# Venato_Schematic_v1.net
KiCad netlist of a schematic drawn in Altium Designer
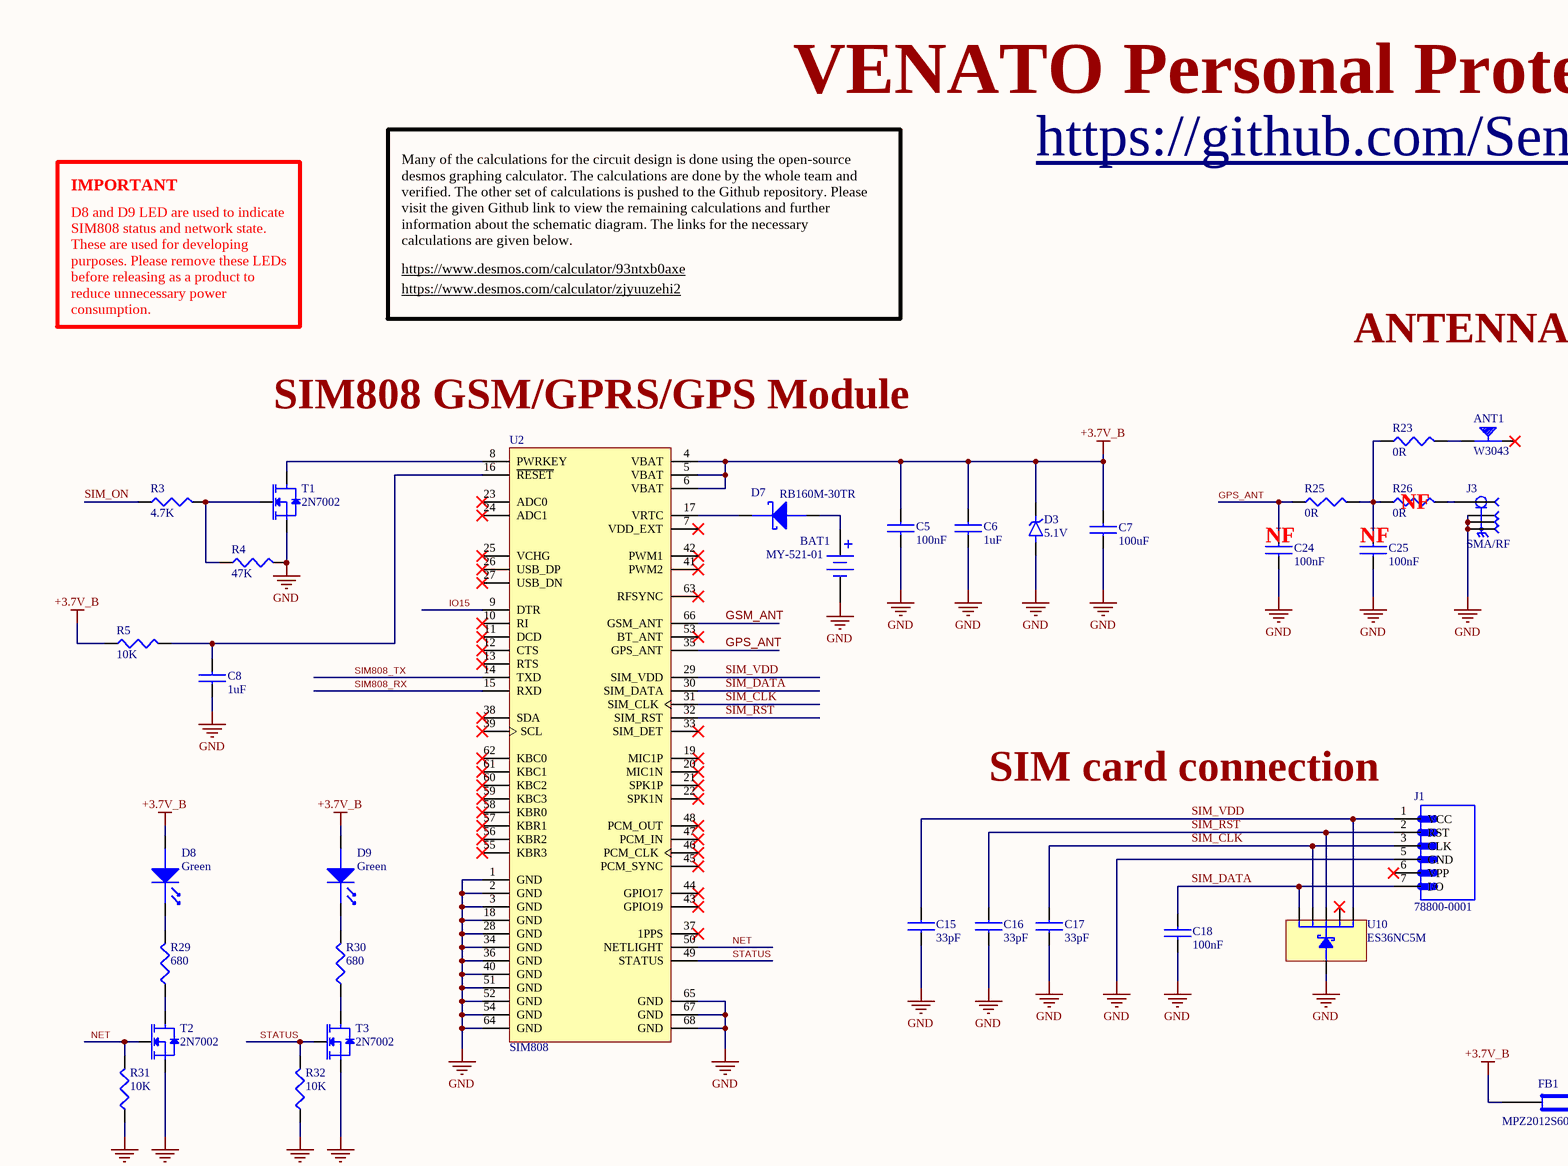
[diagram p0: Venato_Schematic_v1.SchDoc, top left]
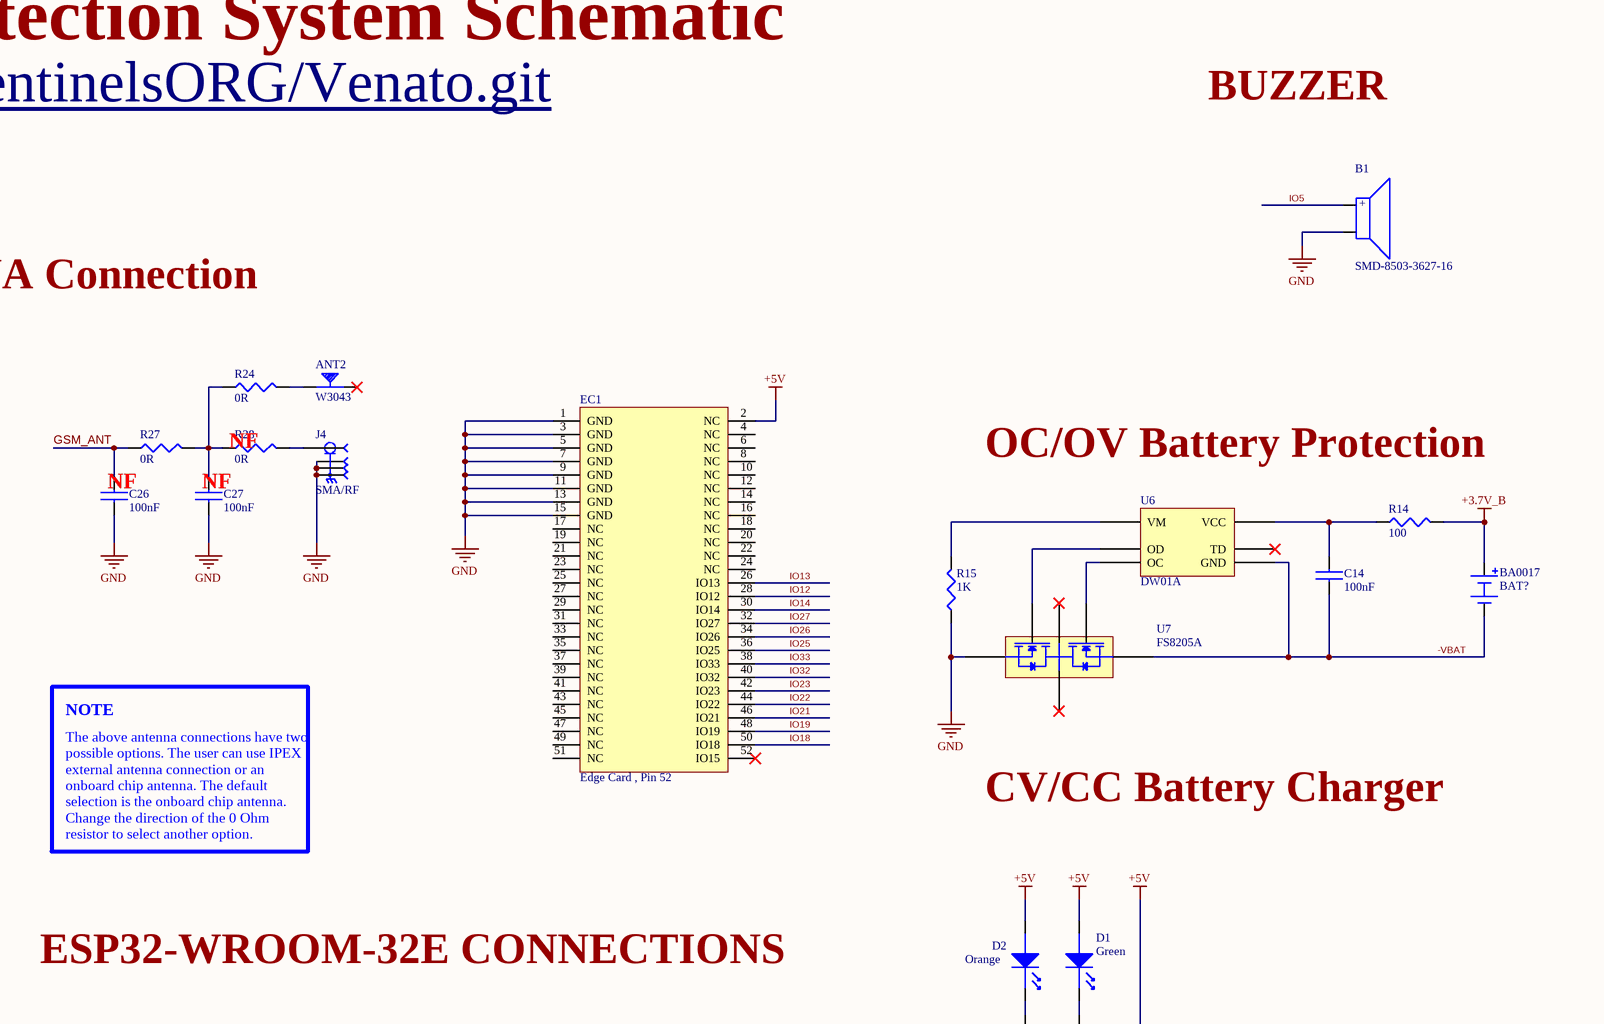
[diagram p1: Venato_Schematic_v1.SchDoc, top right]
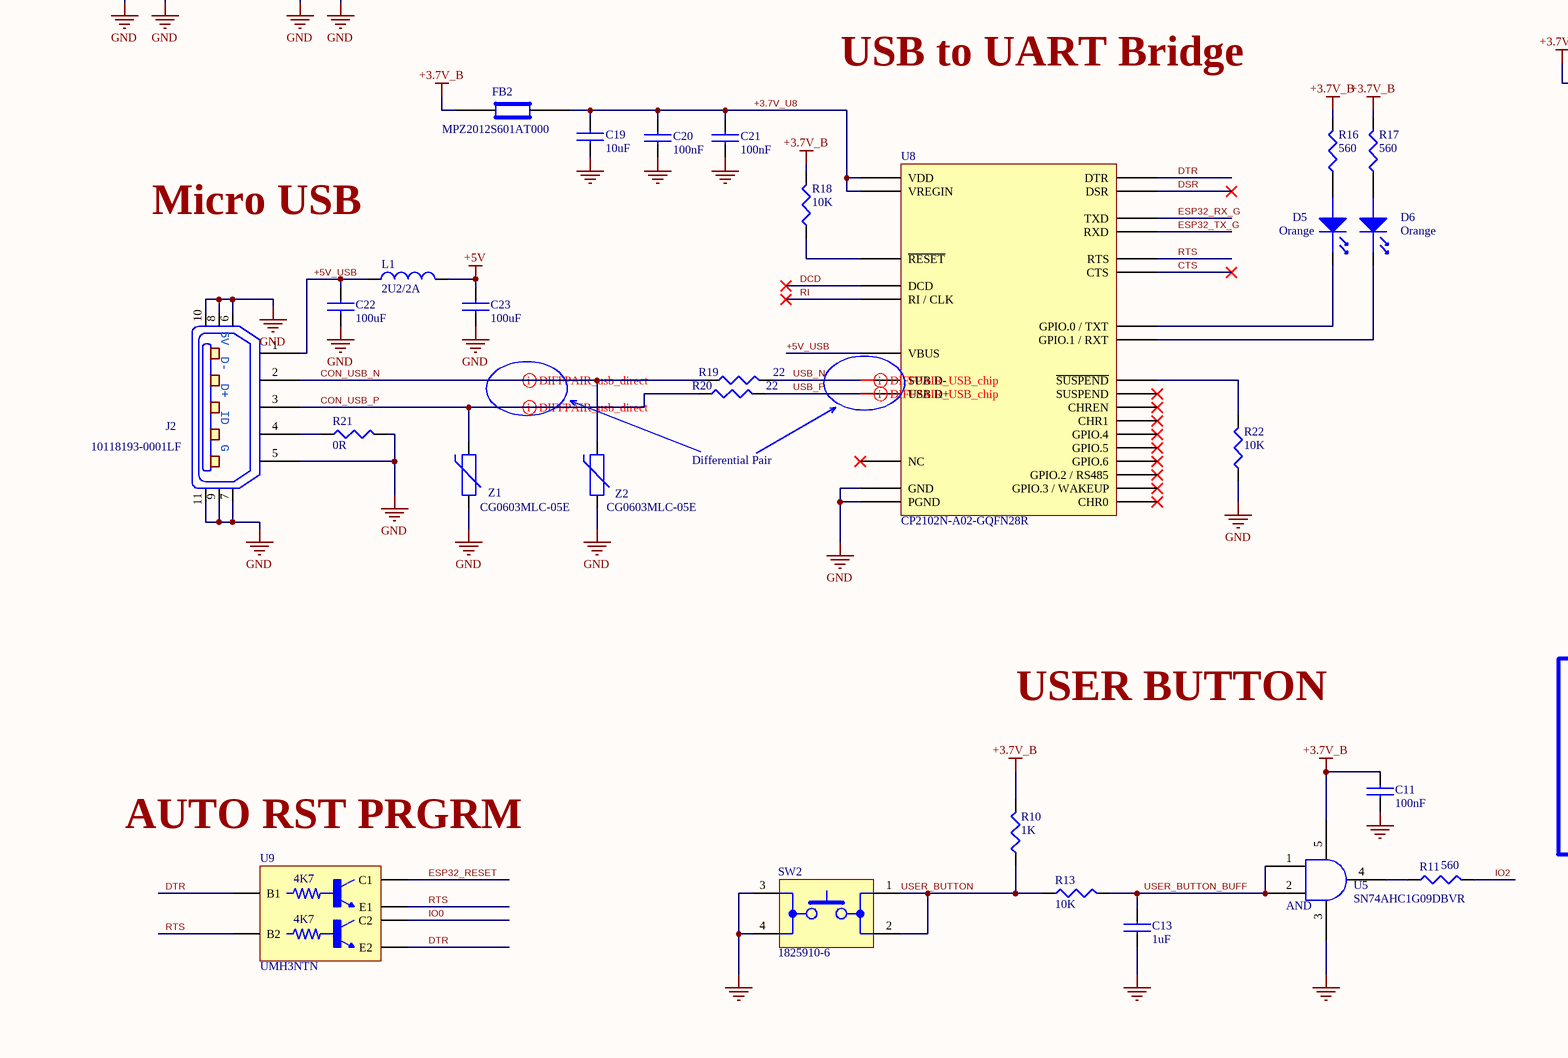
[diagram p2: Venato_Schematic_v1.SchDoc, bottom left]
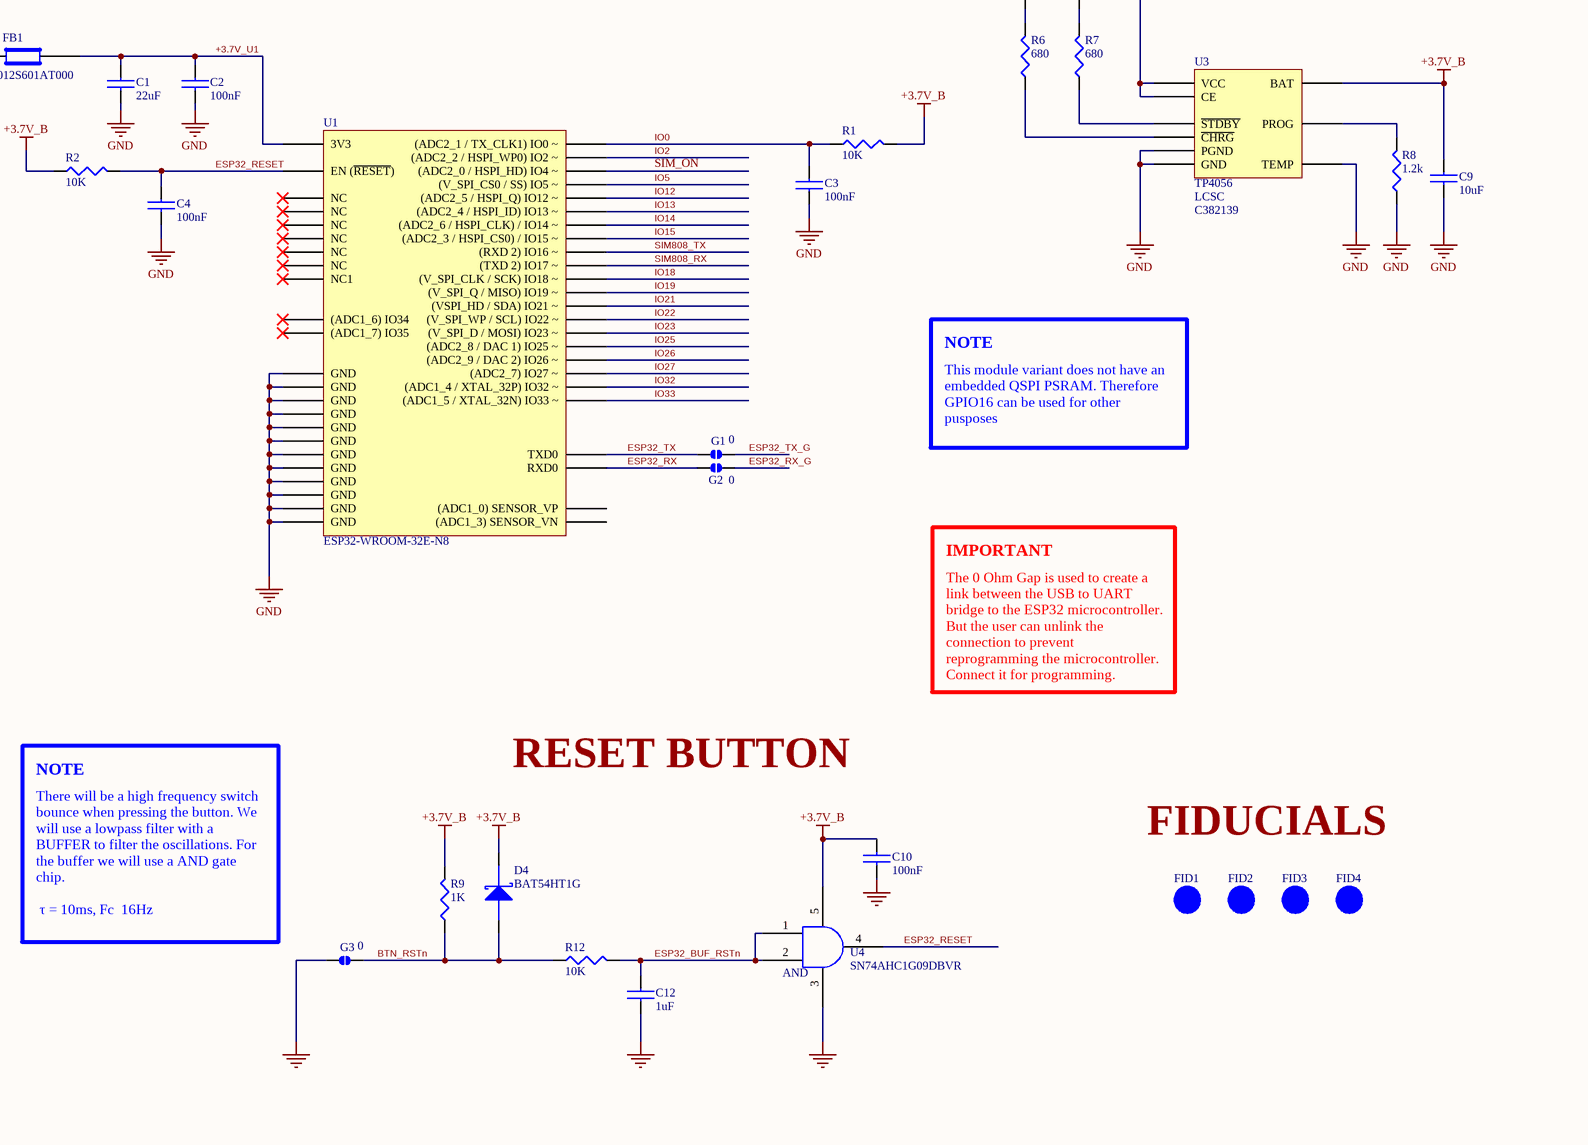
[diagram p3: Venato_Schematic_v1.SchDoc, bottom right]

(export (version "E")
  (design (tool "Eeschema 10.0.6"))
  (components
    (comp (ref "ANT1")
      (value "W3043")
      (footprint "W3010")
      (description "Antenna Ceramic Monopole 4dB Gain 2483.5MHz SMD")
      (fields (field (name "MANUFACTURER") "Pulse"))
      (libsource (lib "schmaticSMDv1") (part "W3043"))
    )
    (comp (ref "ANT2")
      (value "W3043")
      (footprint "W3010")
      (description "Antenna Ceramic Monopole 4dB Gain 2483.5MHz SMD")
      (fields (field (name "MANUFACTURER") "Pulse"))
      (libsource (lib "schmaticSMDv1") (part "W3043"))
    )
    (comp (ref "B1")
      (value "SMD-8503-3627-16")
      (footprint "SMD-8503-3627-16O")
      (description "SMD Buzzers ROHS")
      (fields (field (name "MANUFACTURER") "S&S"))
      (libsource (lib "schmaticSMDv1") (part "SMD-8503-3627-16"))
    )
    (comp (ref "BA0017")
      (value "BAT?")
      (footprint "Battery")
      (libsource (lib "schmaticSMDv1") (part "BA0017"))
    )
    (comp (ref "BAT1")
      (value "MY-521-01")
      (footprint "My-521-01")
      (description "Battery button SR521 SMD Battery Connectors ROHS")
      (fields (field (name "MANUFACTURER") "MYoung"))
      (libsource (lib "schmaticSMDv1") (part "MY-521-01"))
    )
    (comp (ref "C1")
      (value "22uF")
      (footprint "C0805")
      (description "CAP CER 22UF 25V X5R 0805")
      (fields
        (field (name "MANUFACTURER") "Samsung")
        (field (name "MANUFACTURER PART NUMBER") "CL21A226MAQNNNE")
      )
      (libsource (lib "schmaticSMDv1") (part "CL21A226MAQNNNE"))
    )
    (comp (ref "C2")
      (value "100nF")
      (footprint "C0805")
      (description "Cap Ceramic 0.1uF 50V X7R 10% Pad SMD 0805 125°C Automotive T/R")
      (fields
        (field (name "MANUFACTURER") "TDK")
        (field (name "MANUFACTURER PART NUMBER") "CGA4J2X7R1H104K125AM")
      )
      (libsource (lib "schmaticSMDv1") (part "CGA4J2X7R1H104K125AM"))
    )
    (comp (ref "C3")
      (value "100nF")
      (footprint "C0805")
      (description "Cap Ceramic 0.1uF 50V X7R 10% Pad SMD 0805 125°C Automotive T/R")
      (fields
        (field (name "MANUFACTURER") "TDK")
        (field (name "MANUFACTURER PART NUMBER") "CGA4J2X7R1H104K125AM")
      )
      (libsource (lib "schmaticSMDv1") (part "CGA4J2X7R1H104K125AM"))
    )
    (comp (ref "C4")
      (value "100nF")
      (footprint "C0805")
      (description "Cap Ceramic 0.1uF 50V X7R 10% Pad SMD 0805 125°C Automotive T/R")
      (fields
        (field (name "MANUFACTURER") "TDK")
        (field (name "MANUFACTURER PART NUMBER") "CGA4J2X7R1H104K125AM")
      )
      (libsource (lib "schmaticSMDv1") (part "CGA4J2X7R1H104K125AM"))
    )
    (comp (ref "C5")
      (value "100nF")
      (footprint "C0805")
      (description "Cap Ceramic 0.1uF 50V X7R 10% Pad SMD 0805 125°C Automotive T/R")
      (fields
        (field (name "MANUFACTURER") "TDK")
        (field (name "MANUFACTURER PART NUMBER") "CGA4J2X7R1H104K125AM")
      )
      (libsource (lib "schmaticSMDv1") (part "CGA4J2X7R1H104K125AM"))
    )
    (comp (ref "C6")
      (value "1uF")
      (footprint "C0805")
      (description "0805 1 uF 50 V ±10% Tolerance X7R Multilayer Ceramic Chip Capacitor")
      (fields
        (field (name "MANUFACTURER") "Murata")
        (field (name "MANUFACTURER PART NUMBER") "GRM21BR71H105KA12L")
      )
      (libsource (lib "schmaticSMDv1") (part "GRM21BR71H105KA12L"))
    )
    (comp (ref "C7")
      (value "100uF")
      (footprint "C0805")
      (description "0805 100 uF 6.3 V ±20% Tolerance X5R Multilayer Ceramic Chip Capacitor")
      (fields
        (field (name "MANUFACTURER") "Murata")
        (field (name "MANUFACTURER PART NUMBER") "GRM21BR60J107ME15L")
      )
      (libsource (lib "schmaticSMDv1") (part "GRM21BR60J107ME15L"))
    )
    (comp (ref "C8")
      (value "1uF")
      (footprint "C0805")
      (fields
        (field (name "MANUFACTURER") "TDK")
        (field (name "MANUFACTURER PART NUMBER") "C2012X5R1E105K125AA")
        (field (name "TOLERANCE") "10%")
      )
      (libsource (lib "schmaticSMDv1") (part "C2012X5R1E105K125AA"))
    )
    (comp (ref "C9")
      (value "10uF")
      (footprint "C0805")
      (description "Cap Ceramic 10uF 10V X7S 20% Pad SMD 0805 125°C Low ESR Automotive T/R")
      (fields
        (field (name "MANUFACTURER") "TDK")
        (field (name "MANUFACTURER PART NUMBER") "CGA4J3X7S1A106M125AB")
      )
      (libsource (lib "schmaticSMDv1") (part "CGA4J3X7S1A106M125AB"))
    )
    (comp (ref "C10")
      (value "100nF")
      (footprint "C0805")
      (description "Cap Ceramic 0.1uF 50V X7R 10% Pad SMD 0805 125°C Automotive T/R")
      (fields
        (field (name "MANUFACTURER") "TDK")
        (field (name "MANUFACTURER PART NUMBER") "CGA4J2X7R1H104K125AM")
      )
      (libsource (lib "atmega_shlib") (part "CGA4J2X7R1H104K125AM"))
    )
    (comp (ref "C11")
      (value "100nF")
      (footprint "C0805")
      (description "Cap Ceramic 0.1uF 50V X7R 10% Pad SMD 0805 125°C Automotive T/R")
      (fields
        (field (name "MANUFACTURER") "TDK")
        (field (name "MANUFACTURER PART NUMBER") "CGA4J2X7R1H104K125AM")
      )
      (libsource (lib "atmega_shlib") (part "CGA4J2X7R1H104K125AM"))
    )
    (comp (ref "C12")
      (value "1uF")
      (footprint "C0805")
      (fields
        (field (name "MANUFACTURER") "TDK")
        (field (name "MANUFACTURER PART NUMBER") "C2012X5R1E105K125AA")
        (field (name "TOLERANCE") "10%")
      )
      (libsource (lib "schmaticSMDv1") (part "C2012X5R1E105K125AA"))
    )
    (comp (ref "C13")
      (value "1uF")
      (footprint "C0805")
      (fields
        (field (name "MANUFACTURER") "TDK")
        (field (name "MANUFACTURER PART NUMBER") "C2012X5R1E105K125AA")
        (field (name "TOLERANCE") "10%")
      )
      (libsource (lib "schmaticSMDv1") (part "C2012X5R1E105K125AA"))
    )
    (comp (ref "C14")
      (value "100nF")
      (footprint "C0805")
      (description "Cap Ceramic 0.1uF 50V X7R 10% Pad SMD 0805 125°C Automotive T/R")
      (fields
        (field (name "MANUFACTURER") "TDK")
        (field (name "MANUFACTURER PART NUMBER") "CGA4J2X7R1H104K125AM")
      )
      (libsource (lib "schmaticSMDv1") (part "CGA4J2X7R1H104K125AM"))
    )
    (comp (ref "C15")
      (value "33pF")
      (footprint "C0805")
      (description "Cap Ceramic 33pF 50V C0G 5% SMD 0805 125C T/R")
      (fields
        (field (name "MANUFACTURER") "Yageo")
        (field (name "MANUFACTURER PART NUMBER") "CC0805JRNPO9BN330")
      )
      (libsource (lib "schmaticSMDv1") (part "CC0805JRNPO9BN330"))
    )
    (comp (ref "C16")
      (value "33pF")
      (footprint "C0805")
      (description "Cap Ceramic 33pF 50V C0G 5% SMD 0805 125C T/R")
      (fields
        (field (name "MANUFACTURER") "Yageo")
        (field (name "MANUFACTURER PART NUMBER") "CC0805JRNPO9BN330")
      )
      (libsource (lib "schmaticSMDv1") (part "CC0805JRNPO9BN330"))
    )
    (comp (ref "C17")
      (value "33pF")
      (footprint "C0805")
      (description "Cap Ceramic 33pF 50V C0G 5% SMD 0805 125C T/R")
      (fields
        (field (name "MANUFACTURER") "Yageo")
        (field (name "MANUFACTURER PART NUMBER") "CC0805JRNPO9BN330")
      )
      (libsource (lib "schmaticSMDv1") (part "CC0805JRNPO9BN330"))
    )
    (comp (ref "C18")
      (value "100nF")
      (footprint "C0805")
      (description "Cap Ceramic 0.1uF 50V X7R 10% Pad SMD 0805 125°C Automotive T/R")
      (fields
        (field (name "MANUFACTURER") "TDK")
        (field (name "MANUFACTURER PART NUMBER") "CGA4J2X7R1H104K125AM")
      )
      (libsource (lib "schmaticSMDv1") (part "CGA4J2X7R1H104K125AM"))
    )
    (comp (ref "C19")
      (value "10uF")
      (footprint "C0805")
      (description "Cap Ceramic 10uF 10V X7S 20% Pad SMD 0805 125°C Low ESR Automotive T/R")
      (fields
        (field (name "MANUFACTURER") "TDK")
        (field (name "MANUFACTURER PART NUMBER") "CGA4J3X7S1A106M125AB")
      )
      (libsource (lib "atmega_shlib") (part "CGA4J3X7S1A106M125AB"))
    )
    (comp (ref "C20")
      (value "100nF")
      (footprint "C0805")
      (description "Cap Ceramic 0.1uF 50V X7R 10% Pad SMD 0805 125°C Automotive T/R")
      (fields
        (field (name "MANUFACTURER") "TDK")
        (field (name "MANUFACTURER PART NUMBER") "CGA4J2X7R1H104K125AM")
      )
      (libsource (lib "atmega_shlib") (part "CGA4J2X7R1H104K125AM"))
    )
    (comp (ref "C21")
      (value "100nF")
      (footprint "C0805")
      (description "Cap Ceramic 0.1uF 50V X7R 10% Pad SMD 0805 125°C Automotive T/R")
      (fields
        (field (name "MANUFACTURER") "TDK")
        (field (name "MANUFACTURER PART NUMBER") "CGA4J2X7R1H104K125AM")
      )
      (libsource (lib "atmega_shlib") (part "CGA4J2X7R1H104K125AM"))
    )
    (comp (ref "C22")
      (value "100uF")
      (footprint "C0805")
      (description "0805 100 uF 6.3 V ±20% Tolerance X5R Multilayer Ceramic Chip Capacitor")
      (fields
        (field (name "MANUFACTURER") "Murata")
        (field (name "MANUFACTURER PART NUMBER") "GRM21BR60J107ME15L")
      )
      (libsource (lib "schmaticSMDv1") (part "GRM21BR60J107ME15L"))
    )
    (comp (ref "C23")
      (value "100uF")
      (footprint "C0805")
      (description "0805 100 uF 6.3 V ±20% Tolerance X5R Multilayer Ceramic Chip Capacitor")
      (fields
        (field (name "MANUFACTURER") "Murata")
        (field (name "MANUFACTURER PART NUMBER") "GRM21BR60J107ME15L")
      )
      (libsource (lib "schmaticSMDv1") (part "GRM21BR60J107ME15L"))
    )
    (comp (ref "C24")
      (value "100nF")
      (footprint "C0805")
      (description "Cap Ceramic 0.1uF 50V X7R 10% Pad SMD 0805 125°C Automotive T/R")
      (fields
        (field (name "MANUFACTURER") "TDK")
        (field (name "MANUFACTURER PART NUMBER") "CGA4J2X7R1H104K125AM")
      )
      (libsource (lib "schmaticSMDv1") (part "CGA4J2X7R1H104K125AM"))
    )
    (comp (ref "C25")
      (value "100nF")
      (footprint "C0805")
      (description "Cap Ceramic 0.1uF 50V X7R 10% Pad SMD 0805 125°C Automotive T/R")
      (fields
        (field (name "MANUFACTURER") "TDK")
        (field (name "MANUFACTURER PART NUMBER") "CGA4J2X7R1H104K125AM")
      )
      (libsource (lib "schmaticSMDv1") (part "CGA4J2X7R1H104K125AM"))
    )
    (comp (ref "C26")
      (value "100nF")
      (footprint "C0805")
      (description "Cap Ceramic 0.1uF 50V X7R 10% Pad SMD 0805 125°C Automotive T/R")
      (fields
        (field (name "MANUFACTURER") "TDK")
        (field (name "MANUFACTURER PART NUMBER") "CGA4J2X7R1H104K125AM")
      )
      (libsource (lib "schmaticSMDv1") (part "CGA4J2X7R1H104K125AM"))
    )
    (comp (ref "C27")
      (value "100nF")
      (footprint "C0805")
      (description "Cap Ceramic 0.1uF 50V X7R 10% Pad SMD 0805 125°C Automotive T/R")
      (fields
        (field (name "MANUFACTURER") "TDK")
        (field (name "MANUFACTURER PART NUMBER") "CGA4J2X7R1H104K125AM")
      )
      (libsource (lib "schmaticSMDv1") (part "CGA4J2X7R1H104K125AM"))
    )
    (comp (ref "D1")
      (value "Green")
      (footprint "LED0603")
      (description "LED Single Chip Green 570nm 20mA 2-Pin 0603 T/R")
      (fields
        (field (name "MANUFACTURER") "Osram Opto")
        (field (name "MANUFACTURER PART NUMBER") "LGL29K-G2J1-24-Z")
      )
      (libsource (lib "schmaticSMDv1") (part "LGL29K-G2J1-24-Z"))
    )
    (comp (ref "D2")
      (value "Orange")
      (footprint "LED0603")
      (description "Smartled Orange Lc")
      (fields
        (field (name "MANUFACTURER") "Osram Opto")
        (field (name "MANUFACTURER PART NUMBER") "LOL29K-H2K1-24-Z")
      )
      (libsource (lib "schmaticSMDv1") (part "LOL29K-H2K1-24-Z"))
    )
    (comp (ref "D3")
      (value "5.1V")
      (footprint "SOD323")
      (description "Zener Single Diode, 5.1 V, 200 Mw, Sod-323, 6 %, 2, 150 C Rohs Compliant: Yes")
      (fields
        (field (name "MANUFACTURER") "Multicomp")
        (field (name "MANUFACTURER PART NUMBER") "BZT52C5V1S")
      )
      (libsource (lib "schmaticSMDv1") (part "BZT52C5V1S"))
    )
    (comp (ref "D4")
      (value "BAT54HT1G")
      (footprint "SOD323")
      (description "Small Signal Schottky Diode, Single, 30 V, 200 Ma, 800 Mv, 600 Ma, 150 C")
      (fields (field (name "MANUFACTURER") "ON Semiconductor / Fairchild"))
      (libsource (lib "atmega_shlib") (part "BAT54HT1G"))
    )
    (comp (ref "D5")
      (value "Orange")
      (footprint "LED0603")
      (description "Smartled Orange Lc")
      (fields
        (field (name "MANUFACTURER") "Osram Opto")
        (field (name "MANUFACTURER PART NUMBER") "LOL29K-H2K1-24-Z")
      )
      (libsource (lib "atmega_shlib") (part "LOL29K-H2K1-24-Z"))
    )
    (comp (ref "D6")
      (value "Orange")
      (footprint "LED0603")
      (description "Smartled Orange Lc")
      (fields
        (field (name "MANUFACTURER") "Osram Opto")
        (field (name "MANUFACTURER PART NUMBER") "LOL29K-H2K1-24-Z")
      )
      (libsource (lib "atmega_shlib") (part "LOL29K-H2K1-24-Z"))
    )
    (comp (ref "D7")
      (value "RB160M-30TR")
      (footprint "SOD123")
      (description "DIODE SCHOTTKY 30V 1A PMDU")
      (fields (field (name "MANUFACTURER") "Rohm"))
      (libsource (lib "schmaticSMDv1") (part "RB160M-30TR"))
    )
    (comp (ref "D8")
      (value "Green")
      (footprint "LED0603")
      (description "LED Single Chip Green 570nm 20mA 2-Pin 0603 T/R")
      (fields
        (field (name "MANUFACTURER") "Osram Opto")
        (field (name "MANUFACTURER PART NUMBER") "LGL29K-G2J1-24-Z")
      )
      (libsource (lib "schmaticSMDv1") (part "LGL29K-G2J1-24-Z"))
    )
    (comp (ref "D9")
      (value "Green")
      (footprint "LED0603")
      (description "LED Single Chip Green 570nm 20mA 2-Pin 0603 T/R")
      (fields
        (field (name "MANUFACTURER") "Osram Opto")
        (field (name "MANUFACTURER PART NUMBER") "LGL29K-G2J1-24-Z")
      )
      (libsource (lib "schmaticSMDv1") (part "LGL29K-G2J1-24-Z"))
    )
    (comp (ref "EC1")
      (value "Edge Card , Pin 52")
      (footprint "Edge Connector")
      (libsource (lib "schmaticSMDv1") (part "EdgeCard"))
    )
    (comp (ref "FB1")
      (value "MPZ2012S601AT000")
      (footprint "C0805")
      (description "Ferrite Beads Multi-Layer Power 600Ohm 25% 100MHz 2A 100mOhm DCR 0805 T/R")
      (fields (field (name "MANUFACTURER") "TDK"))
      (libsource (lib "schmaticSMDv1") (part "MPZ2012S601AT000"))
    )
    (comp (ref "FB2")
      (value "MPZ2012S601AT000")
      (footprint "C0805")
      (description "Ferrite Beads Multi-Layer Power 600Ohm 25% 100MHz 2A 100mOhm DCR 0805 T/R")
      (fields (field (name "MANUFACTURER") "TDK"))
      (libsource (lib "atmega_shlib") (part "MPZ2012S601AT000"))
    )
    (comp (ref "FID1")
      (value "FID_1MM")
      (footprint "FID_x_420")
      (description "Fisushal 1MM")
      (libsource (lib "atmega_shlib") (part "FID_1MM"))
    )
    (comp (ref "FID2")
      (value "FID_1MM")
      (footprint "FID_x_420")
      (description "Fisushal 1MM")
      (libsource (lib "atmega_shlib") (part "FID_1MM"))
    )
    (comp (ref "FID3")
      (value "FID_1MM")
      (footprint "FID_x_420")
      (description "Fisushal 1MM")
      (libsource (lib "atmega_shlib") (part "FID_1MM"))
    )
    (comp (ref "FID4")
      (value "FID_1MM")
      (footprint "FID_x_420")
      (description "Fisushal 1MM")
      (libsource (lib "atmega_shlib") (part "FID_1MM"))
    )
    (comp (ref "G1")
      (value "0")
      (footprint "R0805_no_3d")
      (description "This is a gap that diconects line. you can connect it using soldier")
      (libsource (lib "schmaticSMDv1") (part "0Ohm gap"))
    )
    (comp (ref "G2")
      (value "0")
      (footprint "R0805_no_3d")
      (description "This is a gap that diconects line. you can connect it using soldier")
      (libsource (lib "schmaticSMDv1") (part "0Ohm gap"))
    )
    (comp (ref "G3")
      (value "0")
      (footprint "R0805_no_3d")
      (description "This is a gap that diconects line. you can connect it using soldier")
      (libsource (lib "schmaticSMDv1") (part "0Ohm gap"))
    )
    (comp (ref "J1")
      (value "78800-0001")
      (footprint "SIM")
      (description "Vertical Surface Mount Memory & SIM Card Connector; with SMT Termination")
      (fields (field (name "MANUFACTURER") "Molex"))
      (libsource (lib "schmaticSMDv1") (part "78800-0001"))
    )
    (comp (ref "J2")
      (value "10118193-0001LF")
      (footprint "10118193-0001LF")
      (description "FCI Right Angle Surface Mount Mount Female USB Connector; 100 V ac; 1.8A")
      (fields (field (name "MANUFACTURER") "Amphenol ICC / FCI"))
      (libsource (lib "atmega_shlib") (part "10118193-0001LF"))
    )
    (comp (ref "J3")
      (value "SMA/RF")
      (footprint "IPEX_20579-001E")
      (description "SMD RF Connectors / Coaxial Connectors ROHS")
      (libsource (lib "schmaticSMDv1") (part "Ipex"))
    )
    (comp (ref "J4")
      (value "SMA/RF")
      (footprint "IPEX_20579-001E")
      (description "SMD RF Connectors / Coaxial Connectors ROHS")
      (libsource (lib "schmaticSMDv1") (part "Ipex"))
    )
    (comp (ref "L1")
      (value "2U2/2A")
      (footprint "CL_inductor")
      (description "Inductor RF Chip Wirewound 2.2uH 20% 100KHz 1.13A 0.104Ohm DCR 1210 T/R")
      (fields
        (field (name "MANUFACTURER") "KEMET")
        (field (name "MANUFACTURER PART NUMBER") "L1210R2R2MDWIT")
      )
      (libsource (lib "atmega_shlib") (part "L1210R2R2MDWIT"))
    )
    (comp (ref "R1")
      (value "10K")
      (footprint "R0805")
      (description "Res SMD 0805 10K 1% 0.125W T.C.100PPM")
      (fields
        (field (name "MANUFACTURER") "Yageo")
        (field (name "MANUFACTURER PART NUMBER") "RC0805FR-0710KL")
      )
      (libsource (lib "schmaticSMDv1") (part "RC0805FR-0710KL"))
    )
    (comp (ref "R2")
      (value "10K")
      (footprint "R0805")
      (description "Res SMD 0805 10K 1% 0.125W T.C.100PPM")
      (fields
        (field (name "MANUFACTURER") "Yageo")
        (field (name "MANUFACTURER PART NUMBER") "RC0805FR-0710KL")
      )
      (libsource (lib "schmaticSMDv1") (part "RC0805FR-0710KL"))
    )
    (comp (ref "R3")
      (value "4.7K")
      (footprint "R0805")
      (description "Res Thick Film 0805 4.7K Ohm 5% 0.125W(1/8W) ±100ppm/C Pad SMD T/R")
      (fields
        (field (name "MANUFACTURER") "Yageo")
        (field (name "MANUFACTURER PART NUMBER") "RC0805JR-074K7L")
      )
      (libsource (lib "schmaticSMDv1") (part "RC0805JR-074K7L"))
    )
    (comp (ref "R4")
      (value "47K")
      (footprint "R0805")
      (description "Res Thick Film 0805 47K Ohm 5% 1/8W Ý100ppm/ÝC SMD Paper T/R")
      (fields
        (field (name "MANUFACTURER") "Yageo")
        (field (name "MANUFACTURER PART NUMBER") "RC0805JR-0747KL")
      )
      (libsource (lib "schmaticSMDv1") (part "RC0805JR-0747KL"))
    )
    (comp (ref "R5")
      (value "10K")
      (footprint "R0805")
      (description "Res SMD 0805 10K 1% 0.125W T.C.100PPM")
      (fields
        (field (name "MANUFACTURER") "Yageo")
        (field (name "MANUFACTURER PART NUMBER") "RC0805FR-0710KL")
      )
      (libsource (lib "schmaticSMDv1") (part "RC0805FR-0710KL"))
    )
    (comp (ref "R6")
      (value "680")
      (footprint "R0805")
      (description "Res Thick Film 0805 680 Ohm 5% 0.125W(1/8W) ±200ppm/C Pad SMD Automotive T/R")
      (fields
        (field (name "MANUFACTURER") "Stackpole Electronics")
        (field (name "MANUFACTURER PART NUMBER") "RMCF0805JT680R")
      )
      (libsource (lib "schmaticSMDv1") (part "RMCF0805JT680R"))
    )
    (comp (ref "R7")
      (value "680")
      (footprint "R0805")
      (description "Res Thick Film 0805 680 Ohm 5% 0.125W(1/8W) ±200ppm/C Pad SMD Automotive T/R")
      (fields
        (field (name "MANUFACTURER") "Stackpole Electronics")
        (field (name "MANUFACTURER PART NUMBER") "RMCF0805JT680R")
      )
      (libsource (lib "schmaticSMDv1") (part "RMCF0805JT680R"))
    )
    (comp (ref "R8")
      (value "1.2k")
      (footprint "R0805")
      (description "Res Thick Film 0805 1.2K Ohm 1% 0.125W(1/8W) ±100ppm/C Pad SMD T/R")
      (fields
        (field (name "MANUFACTURER") "Yageo")
        (field (name "MANUFACTURER PART NUMBER") "RC0805FR-071K2L")
      )
      (libsource (lib "schmaticSMDv1") (part "RC0805FR-071K2L"))
    )
    (comp (ref "R9")
      (value "1K")
      (footprint "R0805")
      (description "Res Thick Film 0805 1KOhm 1% 0.125W(1/8W) 100ppm/C Epoxy Pad SMD T/R")
      (fields
        (field (name "MANUFACTURER") "Yageo")
        (field (name "MANUFACTURER PART NUMBER") "RC0805FR-071KL")
      )
      (libsource (lib "schmaticSMDv1") (part "RC0805FR-071KL"))
    )
    (comp (ref "R10")
      (value "1K")
      (footprint "R0805")
      (description "Res Thick Film 0805 1KOhm 1% 0.125W(1/8W) 100ppm/C Epoxy Pad SMD T/R")
      (fields
        (field (name "MANUFACTURER") "Yageo")
        (field (name "MANUFACTURER PART NUMBER") "RC0805FR-071KL")
      )
      (libsource (lib "schmaticSMDv1") (part "RC0805FR-071KL"))
    )
    (comp (ref "R11")
      (value "560")
      (footprint "R0805")
      (description "Res General Purpose Thick Film 0805 560 Ohm 1% 1/8W ±100ppm/°C Molded Paper T/R")
      (fields
        (field (name "MANUFACTURER") "Yageo")
        (field (name "MANUFACTURER PART NUMBER") "RC0805FR-07560RL")
      )
      (libsource (lib "atmega_shlib") (part "RC0805FR-07560RL"))
    )
    (comp (ref "R12")
      (value "10K")
      (footprint "R0805")
      (description "Res SMD 0805 10K 1% 0.125W T.C.100PPM")
      (fields
        (field (name "MANUFACTURER") "Yageo")
        (field (name "MANUFACTURER PART NUMBER") "RC0805FR-0710KL")
      )
      (libsource (lib "schmaticSMDv1") (part "RC0805FR-0710KL"))
    )
    (comp (ref "R13")
      (value "10K")
      (footprint "R0805")
      (description "Res SMD 0805 10K 1% 0.125W T.C.100PPM")
      (fields
        (field (name "MANUFACTURER") "Yageo")
        (field (name "MANUFACTURER PART NUMBER") "RC0805FR-0710KL")
      )
      (libsource (lib "schmaticSMDv1") (part "RC0805FR-0710KL"))
    )
    (comp (ref "R14")
      (value "100")
      (footprint "R0805")
      (description "Res Thick Film 0805 100 Ohm 1% 1/8W ±100ppm/°C Molded SMD Paper T/R")
      (fields
        (field (name "MANUFACTURER") "Yageo")
        (field (name "MANUFACTURER PART NUMBER") "RC0805FR-07100RL")
      )
      (libsource (lib "schmaticSMDv1") (part "RC0805FR-07100RL"))
    )
    (comp (ref "R15")
      (value "1K")
      (footprint "R0805")
      (description "Res Thick Film 0805 1KOhm 1% 0.125W(1/8W) 100ppm/C Epoxy Pad SMD T/R")
      (fields
        (field (name "MANUFACTURER") "Yageo")
        (field (name "MANUFACTURER PART NUMBER") "RC0805FR-071KL")
      )
      (libsource (lib "schmaticSMDv1") (part "RC0805FR-071KL"))
    )
    (comp (ref "R16")
      (value "560")
      (footprint "R0805")
      (description "Res General Purpose Thick Film 0805 560 Ohm 1% 1/8W ±100ppm/°C Molded Paper T/R")
      (fields
        (field (name "MANUFACTURER") "Yageo")
        (field (name "MANUFACTURER PART NUMBER") "RC0805FR-07560RL")
      )
      (libsource (lib "atmega_shlib") (part "RC0805FR-07560RL"))
    )
    (comp (ref "R17")
      (value "560")
      (footprint "R0805")
      (description "Res General Purpose Thick Film 0805 560 Ohm 1% 1/8W ±100ppm/°C Molded Paper T/R")
      (fields
        (field (name "MANUFACTURER") "Yageo")
        (field (name "MANUFACTURER PART NUMBER") "RC0805FR-07560RL")
      )
      (libsource (lib "atmega_shlib") (part "RC0805FR-07560RL"))
    )
    (comp (ref "R18")
      (value "10K")
      (footprint "R0805")
      (description "Res SMD 0805 10K 1% 0.125W T.C.100PPM")
      (fields
        (field (name "MANUFACTURER") "Yageo")
        (field (name "MANUFACTURER PART NUMBER") "RC0805FR-0710KL")
      )
      (libsource (lib "atmega_shlib") (part "RC0805FR-0710KL"))
    )
    (comp (ref "R19")
      (value "22")
      (footprint "R0805")
      (description "Res SMD 0805 22R 1% 0.125W T.C.100PPM")
      (fields
        (field (name "MANUFACTURER") "Yageo")
        (field (name "MANUFACTURER PART NUMBER") "RC0805FR-0722RL")
      )
      (libsource (lib "atmega_shlib") (part "RC0805FR-0722RL"))
    )
    (comp (ref "R20")
      (value "22")
      (footprint "R0805")
      (description "Res SMD 0805 22R 1% 0.125W T.C.100PPM")
      (fields
        (field (name "MANUFACTURER") "Yageo")
        (field (name "MANUFACTURER PART NUMBER") "RC0805FR-0722RL")
      )
      (libsource (lib "atmega_shlib") (part "RC0805FR-0722RL"))
    )
    (comp (ref "R21")
      (value "0R")
      (footprint "R0805")
      (description "RC Series 0805 0.125 W 0 Ohm Jumper Surface Mount Thick Film Chip Resistor")
      (fields
        (field (name "MANUFACTURER") "Yageo")
        (field (name "MANUFACTURER PART NUMBER") "RC0805JR-070RL")
      )
      (libsource (lib "atmega_shlib") (part "RC0805JR-070RL"))
    )
    (comp (ref "R22")
      (value "10K")
      (footprint "R0805")
      (description "Res SMD 0805 10K 1% 0.125W T.C.100PPM")
      (fields
        (field (name "MANUFACTURER") "Yageo")
        (field (name "MANUFACTURER PART NUMBER") "RC0805FR-0710KL")
      )
      (libsource (lib "atmega_shlib") (part "RC0805FR-0710KL"))
    )
    (comp (ref "R23")
      (value "0R")
      (footprint "R0805")
      (description "RC Series 0805 0.125 W 0 Ohm Jumper Surface Mount Thick Film Chip Resistor")
      (fields
        (field (name "MANUFACTURER") "Yageo")
        (field (name "MANUFACTURER PART NUMBER") "RC0805JR-070RL")
      )
      (libsource (lib "schmaticSMDv1") (part "RC0805JR-070RL"))
    )
    (comp (ref "R24")
      (value "0R")
      (footprint "R0805")
      (description "RC Series 0805 0.125 W 0 Ohm Jumper Surface Mount Thick Film Chip Resistor")
      (fields
        (field (name "MANUFACTURER") "Yageo")
        (field (name "MANUFACTURER PART NUMBER") "RC0805JR-070RL")
      )
      (libsource (lib "schmaticSMDv1") (part "RC0805JR-070RL"))
    )
    (comp (ref "R25")
      (value "0R")
      (footprint "R0805")
      (description "RC Series 0805 0.125 W 0 Ohm Jumper Surface Mount Thick Film Chip Resistor")
      (fields
        (field (name "MANUFACTURER") "Yageo")
        (field (name "MANUFACTURER PART NUMBER") "RC0805JR-070RL")
      )
      (libsource (lib "schmaticSMDv1") (part "RC0805JR-070RL"))
    )
    (comp (ref "R26")
      (value "0R")
      (footprint "R0805")
      (description "RC Series 0805 0.125 W 0 Ohm Jumper Surface Mount Thick Film Chip Resistor")
      (fields
        (field (name "MANUFACTURER") "Yageo")
        (field (name "MANUFACTURER PART NUMBER") "RC0805JR-070RL")
      )
      (libsource (lib "schmaticSMDv1") (part "RC0805JR-070RL"))
    )
    (comp (ref "R27")
      (value "0R")
      (footprint "R0805")
      (description "RC Series 0805 0.125 W 0 Ohm Jumper Surface Mount Thick Film Chip Resistor")
      (fields
        (field (name "MANUFACTURER") "Yageo")
        (field (name "MANUFACTURER PART NUMBER") "RC0805JR-070RL")
      )
      (libsource (lib "schmaticSMDv1") (part "RC0805JR-070RL"))
    )
    (comp (ref "R28")
      (value "0R")
      (footprint "R0805")
      (description "RC Series 0805 0.125 W 0 Ohm Jumper Surface Mount Thick Film Chip Resistor")
      (fields
        (field (name "MANUFACTURER") "Yageo")
        (field (name "MANUFACTURER PART NUMBER") "RC0805JR-070RL")
      )
      (libsource (lib "schmaticSMDv1") (part "RC0805JR-070RL"))
    )
    (comp (ref "R29")
      (value "680")
      (footprint "R0805")
      (description "Res Thick Film 0805 680 Ohm 5% 0.125W(1/8W) ±200ppm/C Pad SMD Automotive T/R")
      (fields
        (field (name "MANUFACTURER") "Stackpole Electronics")
        (field (name "MANUFACTURER PART NUMBER") "RMCF0805JT680R")
      )
      (libsource (lib "schmaticSMDv1") (part "RMCF0805JT680R"))
    )
    (comp (ref "R30")
      (value "680")
      (footprint "R0805")
      (description "Res Thick Film 0805 680 Ohm 5% 0.125W(1/8W) ±200ppm/C Pad SMD Automotive T/R")
      (fields
        (field (name "MANUFACTURER") "Stackpole Electronics")
        (field (name "MANUFACTURER PART NUMBER") "RMCF0805JT680R")
      )
      (libsource (lib "schmaticSMDv1") (part "RMCF0805JT680R"))
    )
    (comp (ref "R31")
      (value "10K")
      (footprint "R0805")
      (description "Res SMD 0805 10K 1% 0.125W T.C.100PPM")
      (fields
        (field (name "MANUFACTURER") "Yageo")
        (field (name "MANUFACTURER PART NUMBER") "RC0805FR-0710KL")
      )
      (libsource (lib "schmaticSMDv1") (part "RC0805FR-0710KL"))
    )
    (comp (ref "R32")
      (value "10K")
      (footprint "R0805")
      (description "Res SMD 0805 10K 1% 0.125W T.C.100PPM")
      (fields
        (field (name "MANUFACTURER") "Yageo")
        (field (name "MANUFACTURER PART NUMBER") "RC0805FR-0710KL")
      )
      (libsource (lib "schmaticSMDv1") (part "RC0805FR-0710KL"))
    )
    (comp (ref "SW2")
      (value "1825910-6")
      (footprint "DIP41825910-6")
      (description "Switch Tactile OFF (ON) SPST Round Button PC Pins 0.05A 24VDC 1.57N Thru-Hole Loose")
      (fields (field (name "MANUFACTURER") "TE Connectivity Alcoswitch"))
      (libsource (lib "atmega_shlib") (part "1825910-6"))
    )
    (comp (ref "T1")
      (value "2N7002")
      (footprint "TRANS_MMBT2907A")
      (description "Transistor Mosfet N-ch 60V 0.3A 3-PIN SOT-23 T/r")
      (libsource (lib "schmaticSMDv1") (part "2N7002"))
    )
    (comp (ref "T2")
      (value "2N7002")
      (footprint "TRANS_MMBT2907A")
      (description "Transistor Mosfet N-ch 60V 0.3A 3-PIN SOT-23 T/r")
      (libsource (lib "schmaticSMDv1") (part "2N7002"))
    )
    (comp (ref "T3")
      (value "2N7002")
      (footprint "TRANS_MMBT2907A")
      (description "Transistor Mosfet N-ch 60V 0.3A 3-PIN SOT-23 T/r")
      (libsource (lib "schmaticSMDv1") (part "2N7002"))
    )
    (comp (ref "U1")
      (value "ESP32-WROOM-32E-N8")
      (footprint "XCVR_ESP32-WROOM-32E_(16MB)")
      (fields (field (name "MANUFACTURER") "Espressif Systems"))
      (libsource (lib "schmaticSMDv1") (part "ESP32-WROOM-32E-N8"))
    )
    (comp (ref "U2")
      (value "SIM808")
      (footprint "XCVR_SIM808")
      (description "GSM/GPRS + GPS + Bluetooth Module SIM808 S2-1060C-Z1F05 SIMCOM; 850/900/1800/1900MHz")
      (libsource (lib "schmaticSMDv1") (part "SIM808"))
    )
    (comp (ref "U3")
      (value "TP4056")
      (footprint "SOP_8")
      (description "Res Thick Film 0805 1.2K Ohm 1% 0.125W(1/8W) ±100ppm/C Pad SMD T/R")
      (fields
        (field (name "MANUFACTURER") "TPOWER")
        (field (name "SUPPLIER 1") "LCSC")
        (field (name "SUPPLIER PART NUMBER 1") "C382139")
        (field (name "TOLERANCE") "1%")
      )
      (libsource (lib "schmaticSMDv1") (part "TP4056"))
    )
    (comp (ref "U4")
      (value "SN74AHC1G09DBVR")
      (footprint "DBV_SOT_5")
      (description "Single 2-input, 2-V to 5.5-V AND gate with open-drain outputs 5-SOT-23 -55 to 125")
      (fields (field (name "MANUFACTURER") "Texas Instruments"))
      (libsource (lib "atmega_shlib") (part "SN74AHC1G09DBVR"))
    )
    (comp (ref "U5")
      (value "SN74AHC1G09DBVR")
      (footprint "DBV_SOT_5")
      (description "Single 2-input, 2-V to 5.5-V AND gate with open-drain outputs 5-SOT-23 -55 to 125")
      (fields (field (name "MANUFACTURER") "Texas Instruments"))
      (libsource (lib "atmega_shlib") (part "SN74AHC1G09DBVR"))
    )
    (comp (ref "U6")
      (value "DW01A")
      (footprint "SOT23-6")
      (description "SOT-23-6L Battery Management ICs ROHS")
      (fields (field (name "MANUFACTURER") "TF"))
      (libsource (lib "schmaticSMDv1") (part "DW01A"))
    )
    (comp (ref "U7")
      (value "FS8205A")
      (footprint "SOT23-6")
      (fields (field (name "MANUFACTURER") "Tech Public"))
      (libsource (lib "schmaticSMDv1") (part "FS8205A"))
    )
    (comp (ref "U8")
      (value "CP2102N-A02-GQFN28R")
      (footprint "WFQFN-28")
      (description "Full Speed USB to UART Bridge USB 2.0 3.3V T/R Automotive 28-Pin QFN EP")
      (fields (field (name "MANUFACTURER") "Silicon Labs"))
      (libsource (lib "schmaticSMDv1") (part "CP2102N-A02-GQFN28R"))
    )
    (comp (ref "U9")
      (value "UMH3NTN")
      (footprint "SOT-363")
      (description "TRANS 2NPN PREBIAS 0.15W UMT6")
      (fields (field (name "MANUFACTURER") "Rohm"))
      (libsource (lib "schmaticSMDv1") (part "UMH3NTN"))
    )
    (comp (ref "U10")
      (value "ES36NC5M")
      (footprint "SOT-363")
      (description "SOT-363 ESD Protection Devices ROHS")
      (fields (field (name "MANUFACTURER") "JESTEK"))
      (libsource (lib "schmaticSMDv1") (part "ES36NC5M"))
    )
    (comp (ref "Z1")
      (value "CG0603MLC-05E")
      (footprint "R0603")
      (description "ESD Suppressor Multilayer Varistor 5V Automotive 2-Pin Case 0603(1608Metric) T/R")
      (fields (field (name "MANUFACTURER") "Bourns") (field (name "VOLTAGE") "5V"))
      (libsource (lib "atmega_shlib") (part "CG0603MLC-05E"))
    )
    (comp (ref "Z2")
      (value "CG0603MLC-05E")
      (footprint "R0603")
      (description "ESD Suppressor Multilayer Varistor 5V Automotive 2-Pin Case 0603(1608Metric) T/R")
      (fields (field (name "MANUFACTURER") "Bourns") (field (name "VOLTAGE") "5V"))
      (libsource (lib "atmega_shlib") (part "CG0603MLC-05E"))
    )
  )
  (nets
    (net (code "1") (name "+3.7V_B") (class "Default")
      (node (ref "BA0017") (pin "1") (pinfunction "1_1") (pintype "passive"))
      (node (ref "C10") (pin "2") (pinfunction "2_2") (pintype "passive"))
      (node (ref "C11") (pin "2") (pinfunction "2_2") (pintype "passive"))
      (node (ref "C5") (pin "2") (pinfunction "2_2") (pintype "passive"))
      (node (ref "C6") (pin "2") (pinfunction "2_2") (pintype "passive"))
      (node (ref "C7") (pin "2") (pinfunction "2_2") (pintype "passive"))
      (node (ref "C9") (pin "2") (pinfunction "2_2") (pintype "passive"))
      (node (ref "D3") (pin "1") (pinfunction "1_1") (pintype "passive"))
      (node (ref "D4") (pin "1") (pinfunction "Ca_1") (pintype "passive"))
      (node (ref "D8") (pin "2") (pinfunction "An_2") (pintype "passive"))
      (node (ref "D9") (pin "2") (pinfunction "An_2") (pintype "passive"))
      (node (ref "FB1") (pin "1") (pinfunction "1_1") (pintype "passive"))
      (node (ref "FB2") (pin "1") (pinfunction "1_1") (pintype "passive"))
      (node (ref "R1") (pin "1") (pinfunction "1_1") (pintype "passive"))
      (node (ref "R10") (pin "2") (pinfunction "2_2") (pintype "passive"))
      (node (ref "R14") (pin "2") (pinfunction "2_2") (pintype "passive"))
      (node (ref "R16") (pin "2") (pinfunction "2_2") (pintype "passive"))
      (node (ref "R17") (pin "2") (pinfunction "2_2") (pintype "passive"))
      (node (ref "R18") (pin "2") (pinfunction "2_2") (pintype "passive"))
      (node (ref "R2") (pin "1") (pinfunction "1_1") (pintype "passive"))
      (node (ref "R5") (pin "1") (pinfunction "1_1") (pintype "passive"))
      (node (ref "R9") (pin "2") (pinfunction "2_2") (pintype "passive"))
      (node (ref "U2") (pin "4") (pinfunction "VBAT_4") (pintype "passive"))
      (node (ref "U2") (pin "5") (pinfunction "VBAT_5") (pintype "passive"))
      (node (ref "U2") (pin "6") (pinfunction "VBAT_6") (pintype "passive"))
      (node (ref "U3") (pin "5") (pinfunction "BAT_5") (pintype "passive"))
      (node (ref "U4") (pin "5") (pinfunction "5_5") (pintype "passive"))
      (node (ref "U5") (pin "5") (pinfunction "5_5") (pintype "passive"))
    )
    (net (code "2") (name "+5V") (class "Default")
      (node (ref "C23") (pin "2") (pinfunction "2_2") (pintype "passive"))
      (node (ref "D1") (pin "2") (pinfunction "An_2") (pintype "passive"))
      (node (ref "D2") (pin "2") (pinfunction "An_2") (pintype "passive"))
      (node (ref "EC1") (pin "2") (pinfunction "NC_2") (pintype "passive"))
      (node (ref "L1") (pin "2") (pinfunction "2_2") (pintype "passive"))
      (node (ref "U3") (pin "4") (pinfunction "VCC_4") (pintype "passive"))
      (node (ref "U3") (pin "8") (pinfunction "CE_8") (pintype "passive"))
    )
    (net (code "3") (name "/+3.7V_U1") (class "Default")
      (node (ref "C1") (pin "2") (pinfunction "2_2") (pintype "passive"))
      (node (ref "C2") (pin "2") (pinfunction "2_2") (pintype "passive"))
      (node (ref "FB1") (pin "2") (pinfunction "2_2") (pintype "passive"))
      (node (ref "U1") (pin "2") (pinfunction "3V3_2") (pintype "power_in"))
    )
    (net (code "4") (name "/+3.7V_U8") (class "Default")
      (node (ref "C19") (pin "2") (pinfunction "2_2") (pintype "passive"))
      (node (ref "C20") (pin "2") (pinfunction "2_2") (pintype "passive"))
      (node (ref "C21") (pin "2") (pinfunction "2_2") (pintype "passive"))
      (node (ref "FB2") (pin "2") (pinfunction "2_2") (pintype "passive"))
      (node (ref "U8") (pin "6") (pinfunction "VDD_6") (pintype "passive"))
      (node (ref "U8") (pin "7") (pinfunction "VREGIN_7") (pintype "passive"))
    )
    (net (code "5") (name "/+5V_USB") (class "Default")
      (node (ref "C22") (pin "2") (pinfunction "2_2") (pintype "passive"))
      (node (ref "J2") (pin "1") (pinfunction "1_1") (pintype "passive"))
      (node (ref "L1") (pin "1") (pinfunction "1_1") (pintype "passive"))
      (node (ref "U8") (pin "8") (pinfunction "VBUS_8") (pintype "passive"))
    )
    (net (code "6") (name "/-VBAT") (class "Default")
      (node (ref "BA0017") (pin "2") (pinfunction "2_2") (pintype "passive"))
      (node (ref "C14") (pin "1") (pinfunction "1_1") (pintype "passive"))
      (node (ref "U6") (pin "6") (pinfunction "GND_6") (pintype "passive"))
      (node (ref "U7") (pin "3") (pinfunction "S2_3") (pintype "passive"))
    )
    (net (code "8") (name "/BTN_RSTn") (class "Default")
      (node (ref "D4") (pin "2") (pinfunction "An_2") (pintype "passive"))
      (node (ref "G3") (pin "2") (pinfunction "2_2") (pintype "passive"))
      (node (ref "R12") (pin "1") (pinfunction "1_1") (pintype "passive"))
      (node (ref "R9") (pin "1") (pinfunction "1_1") (pintype "passive"))
    )
    (net (code "9") (name "/CON_USB_N") (class "Default")
      (node (ref "J2") (pin "2") (pinfunction "2_2") (pintype "passive"))
      (node (ref "R19") (pin "1") (pinfunction "1_1") (pintype "passive"))
      (node (ref "Z2") (pin "2") (pinfunction "2_2") (pintype "passive"))
    )
    (net (code "10") (name "/CON_USB_P") (class "Default")
      (node (ref "J2") (pin "3") (pinfunction "3_3") (pintype "passive"))
      (node (ref "R20") (pin "1") (pinfunction "1_1") (pintype "passive"))
      (node (ref "Z1") (pin "2") (pinfunction "2_2") (pintype "passive"))
    )
    (net (code "11") (name "/CTS") (class "Default")
      (node (ref "U8") (pin "23") (pinfunction "CTS_23") (pintype "passive+no_connect"))
    )
    (net (code "12") (name "/DCD") (class "Default")
      (node (ref "U8") (pin "1") (pinfunction "DCD_1") (pintype "passive+no_connect"))
    )
    (net (code "13") (name "/DSR") (class "Default")
      (node (ref "U8") (pin "27") (pinfunction "DSR_27") (pintype "passive+no_connect"))
    )
    (net (code "14") (name "/DTR") (class "Default")
      (node (ref "U8") (pin "28") (pinfunction "DTR_28") (pintype "passive"))
      (node (ref "U9") (pin "2") (pinfunction "B1_2") (pintype "passive"))
      (node (ref "U9") (pin "4") (pinfunction "E2_4") (pintype "passive"))
    )
    (net (code "15") (name "/ESP32_BUF_RSTn") (class "Default")
      (node (ref "C12") (pin "1") (pinfunction "1_1") (pintype "passive"))
      (node (ref "R12") (pin "2") (pinfunction "2_2") (pintype "passive"))
      (node (ref "U4") (pin "1") (pinfunction "1_1") (pintype "passive"))
      (node (ref "U4") (pin "2") (pinfunction "2_2") (pintype "passive"))
    )
    (net (code "16") (name "/ESP32_RESET") (class "Default")
      (node (ref "C4") (pin "2") (pinfunction "2_2") (pintype "passive"))
      (node (ref "R2") (pin "2") (pinfunction "2_2") (pintype "passive"))
      (node (ref "U1") (pin "3") (pinfunction "EN_(~{RESET})_3") (pintype "passive"))
      (node (ref "U4") (pin "4") (pinfunction "4_4") (pintype "passive"))
      (node (ref "U9") (pin "6") (pinfunction "C1_6") (pintype "passive"))
    )
    (net (code "17") (name "/ESP32_RX") (class "Default")
      (node (ref "G2") (pin "1") (pinfunction "1_1") (pintype "passive"))
      (node (ref "U1") (pin "34") (pinfunction "RXD0_34") (pintype "passive"))
    )
    (net (code "18") (name "/ESP32_RX_G") (class "Default")
      (node (ref "G2") (pin "2") (pinfunction "2_2") (pintype "passive"))
      (node (ref "U8") (pin "26") (pinfunction "TXD_26") (pintype "passive"))
    )
    (net (code "19") (name "/ESP32_TX") (class "Default")
      (node (ref "G1") (pin "1") (pinfunction "1_1") (pintype "passive"))
      (node (ref "U1") (pin "35") (pinfunction "TXD0_35") (pintype "passive"))
    )
    (net (code "20") (name "/ESP32_TX_G") (class "Default")
      (node (ref "G1") (pin "2") (pinfunction "2_2") (pintype "passive"))
      (node (ref "U8") (pin "25") (pinfunction "RXD_25") (pintype "passive"))
    )
    (net (code "21") (name "/GPS_ANT") (class "Default")
      (node (ref "C24") (pin "2") (pinfunction "2_2") (pintype "passive"))
      (node (ref "R25") (pin "1") (pinfunction "1_1") (pintype "passive"))
      (node (ref "U2") (pin "35") (pinfunction "GPS_ANT_35") (pintype "passive"))
    )
    (net (code "22") (name "/GSM_ANT") (class "Default")
      (node (ref "C26") (pin "2") (pinfunction "2_2") (pintype "passive"))
      (node (ref "R27") (pin "1") (pinfunction "1_1") (pintype "passive"))
      (node (ref "U2") (pin "66") (pinfunction "GSM_ANT_66") (pintype "passive"))
    )
    (net (code "23") (name "/IO0") (class "Default")
      (node (ref "C3") (pin "2") (pinfunction "2_2") (pintype "passive"))
      (node (ref "R1") (pin "2") (pinfunction "2_2") (pintype "passive"))
      (node (ref "U1") (pin "25") (pinfunction "(ADC2_1_/_TX_CLK1)_IO0_~_25") (pintype "passive"))
      (node (ref "U9") (pin "3") (pinfunction "C2_3") (pintype "passive"))
    )
    (net (code "24") (name "/IO2") (class "Default")
      (node (ref "R11") (pin "2") (pinfunction "2_2") (pintype "passive"))
      (node (ref "U1") (pin "24") (pinfunction "(ADC2_2_/_HSPI_WP0)_IO2_~_24") (pintype "passive"))
    )
    (net (code "25") (name "/IO5") (class "Default")
      (node (ref "B1") (pin "1") (pinfunction "1_1") (pintype "passive"))
      (node (ref "U1") (pin "29") (pinfunction "(V_SPI_CS0_/_SS)_IO5_~_29") (pintype "passive"))
    )
    (net (code "26") (name "/IO12") (class "Default")
      (node (ref "EC1") (pin "28") (pinfunction "IO12_28") (pintype "passive"))
      (node (ref "U1") (pin "14") (pinfunction "(ADC2_5_/_HSPI_Q)_IO12_~_14") (pintype "passive"))
    )
    (net (code "27") (name "/IO13") (class "Default")
      (node (ref "EC1") (pin "26") (pinfunction "IO13_26") (pintype "passive"))
      (node (ref "U1") (pin "16") (pinfunction "(ADC2_4_/_HSPI_ID)_IO13_~_16") (pintype "passive"))
    )
    (net (code "28") (name "/IO14") (class "Default")
      (node (ref "EC1") (pin "30") (pinfunction "IO14_30") (pintype "passive"))
      (node (ref "U1") (pin "13") (pinfunction "(ADC2_6_/_HSPI_CLK)_/_IO14_~_13") (pintype "passive"))
    )
    (net (code "29") (name "/IO15") (class "Default")
      (node (ref "U1") (pin "23") (pinfunction "(ADC2_3_/_HSPI_CS0)_/_IO15_~_23") (pintype "passive"))
      (node (ref "U2") (pin "9") (pinfunction "DTR_9") (pintype "passive"))
    )
    (net (code "30") (name "/IO18") (class "Default")
      (node (ref "EC1") (pin "50") (pinfunction "IO18_50") (pintype "passive"))
      (node (ref "U1") (pin "30") (pinfunction "(V_SPI_CLK_/_SCK)_IO18_~_30") (pintype "passive"))
    )
    (net (code "31") (name "/IO19") (class "Default")
      (node (ref "EC1") (pin "48") (pinfunction "IO19_48") (pintype "passive"))
      (node (ref "U1") (pin "31") (pinfunction "(V_SPI_Q_/_MISO)_IO19_~_31") (pintype "passive"))
    )
    (net (code "32") (name "/IO21") (class "Default")
      (node (ref "EC1") (pin "46") (pinfunction "IO21_46") (pintype "passive"))
      (node (ref "U1") (pin "33") (pinfunction "(VSPI_HD_/_SDA)_IO21_~_33") (pintype "passive"))
    )
    (net (code "33") (name "/IO22") (class "Default")
      (node (ref "EC1") (pin "44") (pinfunction "IO22_44") (pintype "passive"))
      (node (ref "U1") (pin "36") (pinfunction "(V_SPI_WP_/_SCL)_IO22_~_36") (pintype "passive"))
    )
    (net (code "34") (name "/IO23") (class "Default")
      (node (ref "EC1") (pin "42") (pinfunction "IO23_42") (pintype "passive"))
      (node (ref "U1") (pin "37") (pinfunction "(V_SPI_D_/_MOSI)_IO23_~_37") (pintype "passive"))
    )
    (net (code "35") (name "/IO25") (class "Default")
      (node (ref "EC1") (pin "36") (pinfunction "IO25_36") (pintype "passive"))
      (node (ref "U1") (pin "10") (pinfunction "(ADC2_8_/_DAC_1)_IO25_~_10") (pintype "passive"))
    )
    (net (code "36") (name "/IO26") (class "Default")
      (node (ref "EC1") (pin "34") (pinfunction "IO26_34") (pintype "passive"))
      (node (ref "U1") (pin "11") (pinfunction "(ADC2_9_/_DAC_2)_IO26_~_11") (pintype "passive"))
    )
    (net (code "37") (name "/IO27") (class "Default")
      (node (ref "EC1") (pin "32") (pinfunction "IO27_32") (pintype "passive"))
      (node (ref "U1") (pin "12") (pinfunction "(ADC2_7)_IO27_~_12") (pintype "passive"))
    )
    (net (code "38") (name "/IO32") (class "Default")
      (node (ref "EC1") (pin "40") (pinfunction "IO32_40") (pintype "passive"))
      (node (ref "U1") (pin "8") (pinfunction "(ADC1_4_/_XTAL_32P)_IO32_~_8") (pintype "passive"))
    )
    (net (code "39") (name "/IO33") (class "Default")
      (node (ref "EC1") (pin "38") (pinfunction "IO33_38") (pintype "passive"))
      (node (ref "U1") (pin "9") (pinfunction "(ADC1_5_/_XTAL_32N)_IO33_~_9") (pintype "passive"))
    )
    (net (code "40") (name "/NET") (class "Default")
      (node (ref "R31") (pin "2") (pinfunction "2_2") (pintype "passive"))
      (node (ref "T2") (pin "3") (pinfunction "3_3") (pintype "passive"))
      (node (ref "U2") (pin "50") (pinfunction "NETLIGHT_50") (pintype "passive"))
    )
    (net (code "41") (name "/RI") (class "Default")
      (node (ref "U8") (pin "2") (pinfunction "RI_/_CLK_2") (pintype "passive+no_connect"))
    )
    (net (code "42") (name "/RTS") (class "Default")
      (node (ref "U8") (pin "24") (pinfunction "RTS_24") (pintype "passive"))
      (node (ref "U9") (pin "1") (pinfunction "E1_1") (pintype "passive"))
      (node (ref "U9") (pin "5") (pinfunction "B2_5") (pintype "passive"))
    )
    (net (code "43") (name "/SIM808_RX") (class "Default")
      (node (ref "U1") (pin "28") (pinfunction "(TXD_2)_IO17_~_28") (pintype "passive"))
      (node (ref "U2") (pin "15") (pinfunction "RXD_15") (pintype "passive"))
    )
    (net (code "44") (name "/SIM808_TX") (class "Default")
      (node (ref "U1") (pin "27") (pinfunction "(RXD_2)_IO16_~_27") (pintype "passive"))
      (node (ref "U2") (pin "14") (pinfunction "TXD_14") (pintype "passive"))
    )
    (net (code "45") (name "/SIM_CLK") (class "Default")
      (node (ref "C17") (pin "2") (pinfunction "2_2") (pintype "passive"))
      (node (ref "J1") (pin "3") (pinfunction "CLK_3") (pintype "passive"))
      (node (ref "U10") (pin "3") (pinfunction "3_3") (pintype "passive"))
      (node (ref "U2") (pin "31") (pinfunction "SIM_CLK_31") (pintype "passive"))
    )
    (net (code "46") (name "/SIM_DATA") (class "Default")
      (node (ref "C18") (pin "2") (pinfunction "2_2") (pintype "passive"))
      (node (ref "J1") (pin "7") (pinfunction "I/O_7") (pintype "passive"))
      (node (ref "U10") (pin "1") (pinfunction "1_1") (pintype "passive"))
      (node (ref "U2") (pin "30") (pinfunction "SIM_DATA_30") (pintype "passive"))
    )
    (net (code "47") (name "/SIM_ON") (class "Default")
      (node (ref "R3") (pin "1") (pinfunction "1_1") (pintype "passive"))
      (node (ref "U1") (pin "26") (pinfunction "(ADC2_0_/_HSPI_HD)_IO4_~_26") (pintype "passive"))
    )
    (net (code "48") (name "/SIM_RST") (class "Default")
      (node (ref "C16") (pin "2") (pinfunction "2_2") (pintype "passive"))
      (node (ref "J1") (pin "2") (pinfunction "RST_2") (pintype "passive"))
      (node (ref "U10") (pin "4") (pinfunction "4_4") (pintype "passive"))
      (node (ref "U2") (pin "32") (pinfunction "SIM_RST_32") (pintype "passive"))
    )
    (net (code "49") (name "/SIM_VDD") (class "Default")
      (node (ref "C15") (pin "2") (pinfunction "2_2") (pintype "passive"))
      (node (ref "J1") (pin "1") (pinfunction "VCC_1") (pintype "passive"))
      (node (ref "U10") (pin "6") (pinfunction "6_6") (pintype "passive"))
      (node (ref "U2") (pin "29") (pinfunction "SIM_VDD_29") (pintype "passive"))
    )
    (net (code "50") (name "/STATUS") (class "Default")
      (node (ref "R32") (pin "2") (pinfunction "2_2") (pintype "passive"))
      (node (ref "T3") (pin "3") (pinfunction "3_3") (pintype "passive"))
      (node (ref "U2") (pin "49") (pinfunction "STATUS_49") (pintype "passive"))
    )
    (net (code "51") (name "/USB_N") (class "Default")
      (node (ref "R19") (pin "2") (pinfunction "2_2") (pintype "passive"))
      (node (ref "U8") (pin "5") (pinfunction "SUB_D-_5") (pintype "passive"))
    )
    (net (code "52") (name "/USB_P") (class "Default")
      (node (ref "R20") (pin "2") (pinfunction "2_2") (pintype "passive"))
      (node (ref "U8") (pin "4") (pinfunction "USB_D+_4") (pintype "passive"))
    )
    (net (code "53") (name "/USER_BUTTON") (class "Default")
      (node (ref "R10") (pin "1") (pinfunction "1_1") (pintype "passive"))
      (node (ref "R13") (pin "1") (pinfunction "1_1") (pintype "passive"))
      (node (ref "SW2") (pin "1") (pinfunction "1_1") (pintype "passive"))
      (node (ref "SW2") (pin "2") (pinfunction "2_2") (pintype "passive"))
    )
    (net (code "54") (name "/USER_BUTTON_BUFF") (class "Default")
      (node (ref "C13") (pin "1") (pinfunction "1_1") (pintype "passive"))
      (node (ref "R13") (pin "2") (pinfunction "2_2") (pintype "passive"))
      (node (ref "U5") (pin "1") (pinfunction "1_1") (pintype "passive"))
      (node (ref "U5") (pin "2") (pinfunction "2_2") (pintype "passive"))
    )
    (net (code "55") (name "GND") (class "Default")
      (node (ref "B1") (pin "2") (pinfunction "2_2") (pintype "passive"))
      (node (ref "BAT1") (pin "2") (pinfunction "2_2") (pintype "passive"))
      (node (ref "C1") (pin "1") (pinfunction "1_1") (pintype "passive"))
      (node (ref "C10") (pin "1") (pinfunction "1_1") (pintype "passive"))
      (node (ref "C11") (pin "1") (pinfunction "1_1") (pintype "passive"))
      (node (ref "C12") (pin "2") (pinfunction "2_2") (pintype "passive"))
      (node (ref "C13") (pin "2") (pinfunction "2_2") (pintype "passive"))
      (node (ref "C15") (pin "1") (pinfunction "1_1") (pintype "passive"))
      (node (ref "C16") (pin "1") (pinfunction "1_1") (pintype "passive"))
      (node (ref "C17") (pin "1") (pinfunction "1_1") (pintype "passive"))
      (node (ref "C18") (pin "1") (pinfunction "1_1") (pintype "passive"))
      (node (ref "C19") (pin "1") (pinfunction "1_1") (pintype "passive"))
      (node (ref "C2") (pin "1") (pinfunction "1_1") (pintype "passive"))
      (node (ref "C20") (pin "1") (pinfunction "1_1") (pintype "passive"))
      (node (ref "C21") (pin "1") (pinfunction "1_1") (pintype "passive"))
      (node (ref "C22") (pin "1") (pinfunction "1_1") (pintype "passive"))
      (node (ref "C23") (pin "1") (pinfunction "1_1") (pintype "passive"))
      (node (ref "C24") (pin "1") (pinfunction "1_1") (pintype "passive"))
      (node (ref "C25") (pin "1") (pinfunction "1_1") (pintype "passive"))
      (node (ref "C26") (pin "1") (pinfunction "1_1") (pintype "passive"))
      (node (ref "C27") (pin "1") (pinfunction "1_1") (pintype "passive"))
      (node (ref "C3") (pin "1") (pinfunction "1_1") (pintype "passive"))
      (node (ref "C4") (pin "1") (pinfunction "1_1") (pintype "passive"))
      (node (ref "C5") (pin "1") (pinfunction "1_1") (pintype "passive"))
      (node (ref "C6") (pin "1") (pinfunction "1_1") (pintype "passive"))
      (node (ref "C7") (pin "1") (pinfunction "1_1") (pintype "passive"))
      (node (ref "C8") (pin "1") (pinfunction "1_1") (pintype "passive"))
      (node (ref "C9") (pin "1") (pinfunction "1_1") (pintype "passive"))
      (node (ref "D3") (pin "2") (pinfunction "2_2") (pintype "passive"))
      (node (ref "EC1") (pin "1") (pinfunction "GND_1") (pintype "passive"))
      (node (ref "EC1") (pin "11") (pinfunction "GND_11") (pintype "passive"))
      (node (ref "EC1") (pin "13") (pinfunction "GND_13") (pintype "passive"))
      (node (ref "EC1") (pin "15") (pinfunction "GND_15") (pintype "passive"))
      (node (ref "EC1") (pin "3") (pinfunction "GND_3") (pintype "passive"))
      (node (ref "EC1") (pin "5") (pinfunction "GND_5") (pintype "passive"))
      (node (ref "EC1") (pin "7") (pinfunction "GND_7") (pintype "passive"))
      (node (ref "EC1") (pin "9") (pinfunction "GND_9") (pintype "passive"))
      (node (ref "G3") (pin "1") (pinfunction "1_1") (pintype "passive"))
      (node (ref "J1") (pin "5") (pinfunction "GND_5") (pintype "passive"))
      (node (ref "J2") (pin "10") (pinfunction "10_10") (pintype "passive"))
      (node (ref "J2") (pin "11") (pinfunction "11_11") (pintype "passive"))
      (node (ref "J2") (pin "5") (pinfunction "5_5") (pintype "passive"))
      (node (ref "J2") (pin "6") (pinfunction "6_6") (pintype "passive"))
      (node (ref "J2") (pin "7") (pinfunction "7_7") (pintype "passive"))
      (node (ref "J2") (pin "8") (pinfunction "8_8") (pintype "passive"))
      (node (ref "J2") (pin "9") (pinfunction "9_9") (pintype "passive"))
      (node (ref "J3") (pin "G1") (pinfunction "GROUND_G1") (pintype "passive"))
      (node (ref "J3") (pin "G2") (pinfunction "GROUND_G2") (pintype "passive"))
      (node (ref "J3") (pin "G3") (pinfunction "GROUND_G3") (pintype "passive"))
      (node (ref "J4") (pin "G1") (pinfunction "GROUND_G1") (pintype "passive"))
      (node (ref "J4") (pin "G2") (pinfunction "GROUND_G2") (pintype "passive"))
      (node (ref "J4") (pin "G3") (pinfunction "GROUND_G3") (pintype "passive"))
      (node (ref "R15") (pin "1") (pinfunction "1_1") (pintype "passive"))
      (node (ref "R21") (pin "2") (pinfunction "2_2") (pintype "passive"))
      (node (ref "R22") (pin "1") (pinfunction "1_1") (pintype "passive"))
      (node (ref "R31") (pin "1") (pinfunction "1_1") (pintype "passive"))
      (node (ref "R32") (pin "1") (pinfunction "1_1") (pintype "passive"))
      (node (ref "R4") (pin "2") (pinfunction "2_2") (pintype "passive"))
      (node (ref "R8") (pin "1") (pinfunction "1_1") (pintype "passive"))
      (node (ref "SW2") (pin "3") (pinfunction "3_3") (pintype "passive"))
      (node (ref "SW2") (pin "4") (pinfunction "4_4") (pintype "passive"))
      (node (ref "T1") (pin "1") (pinfunction "1_1") (pintype "passive"))
      (node (ref "T2") (pin "1") (pinfunction "1_1") (pintype "passive"))
      (node (ref "T3") (pin "1") (pinfunction "1_1") (pintype "passive"))
      (node (ref "U1") (pin "1") (pinfunction "GND_1") (pintype "power_in"))
      (node (ref "U1") (pin "15") (pinfunction "GND_15") (pintype "power_in"))
      (node (ref "U1") (pin "38") (pinfunction "GND_38") (pintype "power_in"))
      (node (ref "U1") (pin "39_1") (pinfunction "GND_39_1") (pintype "power_in"))
      (node (ref "U1") (pin "39_2") (pinfunction "GND_39_2") (pintype "power_in"))
      (node (ref "U1") (pin "39_3") (pinfunction "GND_39_3") (pintype "power_in"))
      (node (ref "U1") (pin "39_4") (pinfunction "GND_39_4") (pintype "power_in"))
      (node (ref "U1") (pin "39_5") (pinfunction "GND_39_5") (pintype "power_in"))
      (node (ref "U1") (pin "39_6") (pinfunction "GND_39_6") (pintype "power_in"))
      (node (ref "U1") (pin "39_7") (pinfunction "GND_39_7") (pintype "power_in"))
      (node (ref "U1") (pin "39_8") (pinfunction "GND_39_8") (pintype "power_in"))
      (node (ref "U1") (pin "39_9") (pinfunction "GND_39_9") (pintype "power_in"))
      (node (ref "U10") (pin "2") (pinfunction "2_2") (pintype "passive"))
      (node (ref "U2") (pin "1") (pinfunction "GND_1") (pintype "passive"))
      (node (ref "U2") (pin "18") (pinfunction "GND_18") (pintype "passive"))
      (node (ref "U2") (pin "2") (pinfunction "GND_2") (pintype "passive"))
      (node (ref "U2") (pin "28") (pinfunction "GND_28") (pintype "passive"))
      (node (ref "U2") (pin "3") (pinfunction "GND_3") (pintype "passive"))
      (node (ref "U2") (pin "34") (pinfunction "GND_34") (pintype "passive"))
      (node (ref "U2") (pin "36") (pinfunction "GND_36") (pintype "passive"))
      (node (ref "U2") (pin "40") (pinfunction "GND_40") (pintype "passive"))
      (node (ref "U2") (pin "51") (pinfunction "GND_51") (pintype "passive"))
      (node (ref "U2") (pin "52") (pinfunction "GND_52") (pintype "passive"))
      (node (ref "U2") (pin "54") (pinfunction "GND_54") (pintype "passive"))
      (node (ref "U2") (pin "64") (pinfunction "GND_64") (pintype "passive"))
      (node (ref "U2") (pin "65") (pinfunction "GND_65") (pintype "passive"))
      (node (ref "U2") (pin "67") (pinfunction "GND_67") (pintype "passive"))
      (node (ref "U2") (pin "68") (pinfunction "GND_68") (pintype "passive"))
      (node (ref "U3") (pin "1") (pinfunction "TEMP_1") (pintype "passive"))
      (node (ref "U3") (pin "3") (pinfunction "GND_3") (pintype "passive"))
      (node (ref "U3") (pin "9") (pinfunction "PGND_9") (pintype "passive"))
      (node (ref "U4") (pin "3") (pinfunction "3_3") (pintype "passive"))
      (node (ref "U5") (pin "3") (pinfunction "3_3") (pintype "passive"))
      (node (ref "U7") (pin "1") (pinfunction "S1_1") (pintype "passive"))
      (node (ref "U8") (pin "29") (pinfunction "PGND_29") (pintype "passive"))
      (node (ref "U8") (pin "3") (pinfunction "GND_3") (pintype "passive"))
      (node (ref "Z1") (pin "1") (pinfunction "1_1") (pintype "passive"))
      (node (ref "Z2") (pin "1") (pinfunction "1_1") (pintype "passive"))
    )
    (net (code "56") (name "Net-(ANT1-Pad1)") (class "Default")
      (node (ref "ANT1") (pin "1") (pinfunction "1_1") (pintype "passive"))
      (node (ref "R23") (pin "2") (pinfunction "2_2") (pintype "passive"))
    )
    (net (code "57") (name "Net-(ANT2-Pad1)") (class "Default")
      (node (ref "ANT2") (pin "1") (pinfunction "1_1") (pintype "passive"))
      (node (ref "R24") (pin "2") (pinfunction "2_2") (pintype "passive"))
    )
    (net (code "58") (name "Net-(C25-Pad2)") (class "Default")
      (node (ref "C25") (pin "2") (pinfunction "2_2") (pintype "passive"))
      (node (ref "R23") (pin "1") (pinfunction "1_1") (pintype "passive"))
      (node (ref "R25") (pin "2") (pinfunction "2_2") (pintype "passive"))
      (node (ref "R26") (pin "1") (pinfunction "1_1") (pintype "passive"))
    )
    (net (code "59") (name "Net-(C27-Pad2)") (class "Default")
      (node (ref "C27") (pin "2") (pinfunction "2_2") (pintype "passive"))
      (node (ref "R24") (pin "1") (pinfunction "1_1") (pintype "passive"))
      (node (ref "R27") (pin "2") (pinfunction "2_2") (pintype "passive"))
      (node (ref "R28") (pin "1") (pinfunction "1_1") (pintype "passive"))
    )
    (net (code "60") (name "Net-(D1-Ca)") (class "Default")
      (node (ref "D1") (pin "1") (pinfunction "Ca_1") (pintype "passive"))
      (node (ref "R7") (pin "2") (pinfunction "2_2") (pintype "passive"))
    )
    (net (code "61") (name "Net-(D2-Ca)") (class "Default")
      (node (ref "D2") (pin "1") (pinfunction "Ca_1") (pintype "passive"))
      (node (ref "R6") (pin "2") (pinfunction "2_2") (pintype "passive"))
    )
    (net (code "62") (name "Net-(D5-An)") (class "Default")
      (node (ref "D5") (pin "2") (pinfunction "An_2") (pintype "passive"))
      (node (ref "R16") (pin "1") (pinfunction "1_1") (pintype "passive"))
    )
    (net (code "63") (name "Net-(D5-Ca)") (class "Default")
      (node (ref "D5") (pin "1") (pinfunction "Ca_1") (pintype "passive"))
      (node (ref "U8") (pin "19") (pinfunction "GPIO.0_/_TXT_19") (pintype "passive"))
    )
    (net (code "64") (name "Net-(D6-An)") (class "Default")
      (node (ref "D6") (pin "2") (pinfunction "An_2") (pintype "passive"))
      (node (ref "R17") (pin "1") (pinfunction "1_1") (pintype "passive"))
    )
    (net (code "65") (name "Net-(D6-Ca)") (class "Default")
      (node (ref "D6") (pin "1") (pinfunction "Ca_1") (pintype "passive"))
      (node (ref "U8") (pin "18") (pinfunction "GPIO.1_/_RXT_18") (pintype "passive"))
    )
    (net (code "66") (name "Net-(D7-An)") (class "Default")
      (node (ref "BAT1") (pin "1") (pinfunction "1_1") (pintype "passive"))
      (node (ref "D7") (pin "2") (pinfunction "An_2") (pintype "passive"))
    )
    (net (code "67") (name "Net-(D7-Ca)") (class "Default")
      (node (ref "D7") (pin "1") (pinfunction "Ca_1") (pintype "passive"))
      (node (ref "U2") (pin "17") (pinfunction "VRTC_17") (pintype "passive"))
    )
    (net (code "68") (name "Net-(D8-Ca)") (class "Default")
      (node (ref "D8") (pin "1") (pinfunction "Ca_1") (pintype "passive"))
      (node (ref "R29") (pin "2") (pinfunction "2_2") (pintype "passive"))
    )
    (net (code "69") (name "Net-(D9-Ca)") (class "Default")
      (node (ref "D9") (pin "1") (pinfunction "Ca_1") (pintype "passive"))
      (node (ref "R30") (pin "2") (pinfunction "2_2") (pintype "passive"))
    )
    (net (code "70") (name "Net-(J2-Pad4)") (class "Default")
      (node (ref "J2") (pin "4") (pinfunction "4_4") (pintype "passive"))
      (node (ref "R21") (pin "1") (pinfunction "1_1") (pintype "passive"))
    )
    (net (code "71") (name "Net-(J3-SIGNAL)") (class "Default")
      (node (ref "J3") (pin "1") (pinfunction "SIGNAL_1") (pintype "passive"))
      (node (ref "R26") (pin "2") (pinfunction "2_2") (pintype "passive"))
    )
    (net (code "72") (name "Net-(J4-SIGNAL)") (class "Default")
      (node (ref "J4") (pin "1") (pinfunction "SIGNAL_1") (pintype "passive"))
      (node (ref "R28") (pin "2") (pinfunction "2_2") (pintype "passive"))
    )
    (net (code "73") (name "Net-(R3-Pad2)") (class "Default")
      (node (ref "R3") (pin "2") (pinfunction "2_2") (pintype "passive"))
      (node (ref "R4") (pin "1") (pinfunction "1_1") (pintype "passive"))
      (node (ref "T1") (pin "3") (pinfunction "3_3") (pintype "passive"))
    )
    (net (code "74") (name "Net-(R11-Pad1)") (class "Default")
      (node (ref "R11") (pin "1") (pinfunction "1_1") (pintype "passive"))
      (node (ref "U5") (pin "4") (pinfunction "4_4") (pintype "passive"))
    )
    (net (code "75") (name "Net-(R29-Pad1)") (class "Default")
      (node (ref "R29") (pin "1") (pinfunction "1_1") (pintype "passive"))
      (node (ref "T2") (pin "2") (pinfunction "2_2") (pintype "passive"))
    )
    (net (code "76") (name "Net-(R30-Pad1)") (class "Default")
      (node (ref "R30") (pin "1") (pinfunction "1_1") (pintype "passive"))
      (node (ref "T3") (pin "2") (pinfunction "2_2") (pintype "passive"))
    )
    (net (code "77") (name "Net-(U2-PWRKEY)") (class "Default")
      (node (ref "T1") (pin "2") (pinfunction "2_2") (pintype "passive"))
      (node (ref "U2") (pin "8") (pinfunction "PWRKEY_8") (pintype "passive"))
    )
    (net (code "78") (name "Net-(U2-~{RESET})") (class "Default")
      (node (ref "C8") (pin "2") (pinfunction "2_2") (pintype "passive"))
      (node (ref "R5") (pin "2") (pinfunction "2_2") (pintype "passive"))
      (node (ref "U2") (pin "16") (pinfunction "~{RESET}_16") (pintype "passive"))
    )
    (net (code "79") (name "Net-(U3-PROG)") (class "Default")
      (node (ref "R8") (pin "2") (pinfunction "2_2") (pintype "passive"))
      (node (ref "U3") (pin "2") (pinfunction "PROG_2") (pintype "passive"))
    )
    (net (code "80") (name "Net-(U3-~{CHRG})") (class "Default")
      (node (ref "R6") (pin "1") (pinfunction "1_1") (pintype "passive"))
      (node (ref "U3") (pin "7") (pinfunction "~{CHRG}_7") (pintype "passive"))
    )
    (net (code "81") (name "Net-(U3-~{STDBY})") (class "Default")
      (node (ref "R7") (pin "1") (pinfunction "1_1") (pintype "passive"))
      (node (ref "U3") (pin "6") (pinfunction "~{STDBY}_6") (pintype "passive"))
    )
    (net (code "82") (name "Net-(U6-OC)") (class "Default")
      (node (ref "U6") (pin "3") (pinfunction "OC_3") (pintype "passive"))
      (node (ref "U7") (pin "4") (pinfunction "G2_4") (pintype "passive"))
    )
    (net (code "83") (name "Net-(U6-OD)") (class "Default")
      (node (ref "U6") (pin "1") (pinfunction "OD_1") (pintype "passive"))
      (node (ref "U7") (pin "6") (pinfunction "G1_6") (pintype "passive"))
    )
    (net (code "84") (name "Net-(U6-VCC)") (class "Default")
      (node (ref "C14") (pin "2") (pinfunction "2_2") (pintype "passive"))
      (node (ref "R14") (pin "1") (pinfunction "1_1") (pintype "passive"))
      (node (ref "U6") (pin "5") (pinfunction "VCC_5") (pintype "passive"))
    )
    (net (code "85") (name "Net-(U6-VM)") (class "Default")
      (node (ref "R15") (pin "2") (pinfunction "2_2") (pintype "passive"))
      (node (ref "U6") (pin "2") (pinfunction "VM_2") (pintype "passive"))
    )
    (net (code "86") (name "Net-(U8-~{RESET})") (class "Default")
      (node (ref "R18") (pin "1") (pinfunction "1_1") (pintype "passive"))
      (node (ref "U8") (pin "9") (pinfunction "~{RESET}_9") (pintype "passive"))
    )
    (net (code "87") (name "Net-(U8-~{SUSPEND})") (class "Default")
      (node (ref "R22") (pin "2") (pinfunction "2_2") (pintype "passive"))
      (node (ref "U8") (pin "11") (pinfunction "~{SUSPEND}_11") (pintype "passive"))
    )
    (net (code "88") (name "unconnected-(ANT1-Pad2)") (class "Default")
      (node (ref "ANT1") (pin "2") (pinfunction "2_2") (pintype "passive+no_connect"))
    )
    (net (code "89") (name "unconnected-(ANT2-Pad2)") (class "Default")
      (node (ref "ANT2") (pin "2") (pinfunction "2_2") (pintype "passive+no_connect"))
    )
    (net (code "90") (name "unconnected-(EC1-IO15-Pad52)") (class "Default")
      (node (ref "EC1") (pin "52") (pinfunction "IO15_52") (pintype "passive+no_connect"))
    )
    (net (code "91") (name "unconnected-(EC1-NC-Pad4)") (class "Default")
      (node (ref "EC1") (pin "4") (pinfunction "NC_4") (pintype "passive"))
    )
    (net (code "92") (name "unconnected-(EC1-NC-Pad6)") (class "Default")
      (node (ref "EC1") (pin "6") (pinfunction "NC_6") (pintype "passive"))
    )
    (net (code "93") (name "unconnected-(EC1-NC-Pad8)") (class "Default")
      (node (ref "EC1") (pin "8") (pinfunction "NC_8") (pintype "passive"))
    )
    (net (code "94") (name "unconnected-(EC1-NC-Pad10)") (class "Default")
      (node (ref "EC1") (pin "10") (pinfunction "NC_10") (pintype "passive"))
    )
    (net (code "95") (name "unconnected-(EC1-NC-Pad12)") (class "Default")
      (node (ref "EC1") (pin "12") (pinfunction "NC_12") (pintype "passive"))
    )
    (net (code "96") (name "unconnected-(EC1-NC-Pad14)") (class "Default")
      (node (ref "EC1") (pin "14") (pinfunction "NC_14") (pintype "passive"))
    )
    (net (code "97") (name "unconnected-(EC1-NC-Pad16)") (class "Default")
      (node (ref "EC1") (pin "16") (pinfunction "NC_16") (pintype "passive"))
    )
    (net (code "98") (name "unconnected-(EC1-NC-Pad17)") (class "Default")
      (node (ref "EC1") (pin "17") (pinfunction "NC_17") (pintype "passive"))
    )
    (net (code "99") (name "unconnected-(EC1-NC-Pad18)") (class "Default")
      (node (ref "EC1") (pin "18") (pinfunction "NC_18") (pintype "passive"))
    )
    (net (code "100") (name "unconnected-(EC1-NC-Pad19)") (class "Default")
      (node (ref "EC1") (pin "19") (pinfunction "NC_19") (pintype "passive"))
    )
    (net (code "101") (name "unconnected-(EC1-NC-Pad20)") (class "Default")
      (node (ref "EC1") (pin "20") (pinfunction "NC_20") (pintype "passive"))
    )
    (net (code "102") (name "unconnected-(EC1-NC-Pad21)") (class "Default")
      (node (ref "EC1") (pin "21") (pinfunction "NC_21") (pintype "passive"))
    )
    (net (code "103") (name "unconnected-(EC1-NC-Pad22)") (class "Default")
      (node (ref "EC1") (pin "22") (pinfunction "NC_22") (pintype "passive"))
    )
    (net (code "104") (name "unconnected-(EC1-NC-Pad23)") (class "Default")
      (node (ref "EC1") (pin "23") (pinfunction "NC_23") (pintype "passive"))
    )
    (net (code "105") (name "unconnected-(EC1-NC-Pad24)") (class "Default")
      (node (ref "EC1") (pin "24") (pinfunction "NC_24") (pintype "passive"))
    )
    (net (code "106") (name "unconnected-(EC1-NC-Pad25)") (class "Default")
      (node (ref "EC1") (pin "25") (pinfunction "NC_25") (pintype "passive"))
    )
    (net (code "107") (name "unconnected-(EC1-NC-Pad27)") (class "Default")
      (node (ref "EC1") (pin "27") (pinfunction "NC_27") (pintype "passive"))
    )
    (net (code "108") (name "unconnected-(EC1-NC-Pad29)") (class "Default")
      (node (ref "EC1") (pin "29") (pinfunction "NC_29") (pintype "passive"))
    )
    (net (code "109") (name "unconnected-(EC1-NC-Pad31)") (class "Default")
      (node (ref "EC1") (pin "31") (pinfunction "NC_31") (pintype "passive"))
    )
    (net (code "110") (name "unconnected-(EC1-NC-Pad33)") (class "Default")
      (node (ref "EC1") (pin "33") (pinfunction "NC_33") (pintype "passive"))
    )
    (net (code "111") (name "unconnected-(EC1-NC-Pad35)") (class "Default")
      (node (ref "EC1") (pin "35") (pinfunction "NC_35") (pintype "passive"))
    )
    (net (code "112") (name "unconnected-(EC1-NC-Pad37)") (class "Default")
      (node (ref "EC1") (pin "37") (pinfunction "NC_37") (pintype "passive"))
    )
    (net (code "113") (name "unconnected-(EC1-NC-Pad39)") (class "Default")
      (node (ref "EC1") (pin "39") (pinfunction "NC_39") (pintype "passive"))
    )
    (net (code "114") (name "unconnected-(EC1-NC-Pad41)") (class "Default")
      (node (ref "EC1") (pin "41") (pinfunction "NC_41") (pintype "passive"))
    )
    (net (code "115") (name "unconnected-(EC1-NC-Pad43)") (class "Default")
      (node (ref "EC1") (pin "43") (pinfunction "NC_43") (pintype "passive"))
    )
    (net (code "116") (name "unconnected-(EC1-NC-Pad45)") (class "Default")
      (node (ref "EC1") (pin "45") (pinfunction "NC_45") (pintype "passive"))
    )
    (net (code "117") (name "unconnected-(EC1-NC-Pad47)") (class "Default")
      (node (ref "EC1") (pin "47") (pinfunction "NC_47") (pintype "passive"))
    )
    (net (code "118") (name "unconnected-(EC1-NC-Pad49)") (class "Default")
      (node (ref "EC1") (pin "49") (pinfunction "NC_49") (pintype "passive"))
    )
    (net (code "119") (name "unconnected-(EC1-NC-Pad51)") (class "Default")
      (node (ref "EC1") (pin "51") (pinfunction "NC_51") (pintype "passive"))
    )
    (net (code "120") (name "unconnected-(J1-VPP-Pad6)") (class "Default")
      (node (ref "J1") (pin "6") (pinfunction "VPP_6") (pintype "passive+no_connect"))
    )
    (net (code "121") (name "unconnected-(U1-(ADC1_0)_SENSOR_VP-Pad4)") (class "Default")
      (node (ref "U1") (pin "4") (pinfunction "(ADC1_0)_SENSOR_VP_4") (pintype "passive"))
    )
    (net (code "122") (name "unconnected-(U1-(ADC1_3)_SENSOR_VN-Pad5)") (class "Default")
      (node (ref "U1") (pin "5") (pinfunction "(ADC1_3)_SENSOR_VN_5") (pintype "passive"))
    )
    (net (code "123") (name "unconnected-(U1-(ADC1_6)_IO34-Pad6)") (class "Default")
      (node (ref "U1") (pin "6") (pinfunction "(ADC1_6)_IO34_6") (pintype "passive+no_connect"))
    )
    (net (code "124") (name "unconnected-(U1-(ADC1_7)_IO35-Pad7)") (class "Default")
      (node (ref "U1") (pin "7") (pinfunction "(ADC1_7)_IO35_7") (pintype "passive+no_connect"))
    )
    (net (code "125") (name "unconnected-(U1-NC-Pad17)") (class "Default")
      (node (ref "U1") (pin "17") (pinfunction "NC_17") (pintype "passive+no_connect"))
    )
    (net (code "126") (name "unconnected-(U1-NC-Pad18)") (class "Default")
      (node (ref "U1") (pin "18") (pinfunction "NC_18") (pintype "passive+no_connect"))
    )
    (net (code "127") (name "unconnected-(U1-NC-Pad19)") (class "Default")
      (node (ref "U1") (pin "19") (pinfunction "NC_19") (pintype "passive+no_connect"))
    )
    (net (code "128") (name "unconnected-(U1-NC-Pad20)") (class "Default")
      (node (ref "U1") (pin "20") (pinfunction "NC_20") (pintype "passive+no_connect"))
    )
    (net (code "129") (name "unconnected-(U1-NC-Pad21)") (class "Default")
      (node (ref "U1") (pin "21") (pinfunction "NC_21") (pintype "passive+no_connect"))
    )
    (net (code "130") (name "unconnected-(U1-NC-Pad22)") (class "Default")
      (node (ref "U1") (pin "22") (pinfunction "NC_22") (pintype "passive+no_connect"))
    )
    (net (code "131") (name "unconnected-(U1-NC1-Pad32)") (class "Default")
      (node (ref "U1") (pin "32") (pinfunction "NC1_32") (pintype "passive+no_connect"))
    )
    (net (code "132") (name "unconnected-(U2-1PPS-Pad37)") (class "Default")
      (node (ref "U2") (pin "37") (pinfunction "1PPS_37") (pintype "passive+no_connect"))
    )
    (net (code "133") (name "unconnected-(U2-ADC0-Pad23)") (class "Default")
      (node (ref "U2") (pin "23") (pinfunction "ADC0_23") (pintype "passive+no_connect"))
    )
    (net (code "134") (name "unconnected-(U2-ADC1-Pad24)") (class "Default")
      (node (ref "U2") (pin "24") (pinfunction "ADC1_24") (pintype "passive+no_connect"))
    )
    (net (code "135") (name "unconnected-(U2-BT_ANT-Pad53)") (class "Default")
      (node (ref "U2") (pin "53") (pinfunction "BT_ANT_53") (pintype "passive+no_connect"))
    )
    (net (code "136") (name "unconnected-(U2-CTS-Pad12)") (class "Default")
      (node (ref "U2") (pin "12") (pinfunction "CTS_12") (pintype "passive+no_connect"))
    )
    (net (code "137") (name "unconnected-(U2-DCD-Pad11)") (class "Default")
      (node (ref "U2") (pin "11") (pinfunction "DCD_11") (pintype "passive+no_connect"))
    )
    (net (code "138") (name "unconnected-(U2-GPIO17-Pad44)") (class "Default")
      (node (ref "U2") (pin "44") (pinfunction "GPIO17_44") (pintype "passive+no_connect"))
    )
    (net (code "139") (name "unconnected-(U2-GPIO19-Pad43)") (class "Default")
      (node (ref "U2") (pin "43") (pinfunction "GPIO19_43") (pintype "passive+no_connect"))
    )
    (net (code "140") (name "unconnected-(U2-KBC0-Pad62)") (class "Default")
      (node (ref "U2") (pin "62") (pinfunction "KBC0_62") (pintype "passive+no_connect"))
    )
    (net (code "141") (name "unconnected-(U2-KBC1-Pad61)") (class "Default")
      (node (ref "U2") (pin "61") (pinfunction "KBC1_61") (pintype "passive+no_connect"))
    )
    (net (code "142") (name "unconnected-(U2-KBC2-Pad60)") (class "Default")
      (node (ref "U2") (pin "60") (pinfunction "KBC2_60") (pintype "passive+no_connect"))
    )
    (net (code "143") (name "unconnected-(U2-KBC3-Pad59)") (class "Default")
      (node (ref "U2") (pin "59") (pinfunction "KBC3_59") (pintype "passive+no_connect"))
    )
    (net (code "144") (name "unconnected-(U2-KBR0-Pad58)") (class "Default")
      (node (ref "U2") (pin "58") (pinfunction "KBR0_58") (pintype "passive+no_connect"))
    )
    (net (code "145") (name "unconnected-(U2-KBR1-Pad57)") (class "Default")
      (node (ref "U2") (pin "57") (pinfunction "KBR1_57") (pintype "passive+no_connect"))
    )
    (net (code "146") (name "unconnected-(U2-KBR2-Pad56)") (class "Default")
      (node (ref "U2") (pin "56") (pinfunction "KBR2_56") (pintype "passive+no_connect"))
    )
    (net (code "147") (name "unconnected-(U2-KBR3-Pad55)") (class "Default")
      (node (ref "U2") (pin "55") (pinfunction "KBR3_55") (pintype "passive+no_connect"))
    )
    (net (code "148") (name "unconnected-(U2-MIC1N-Pad20)") (class "Default")
      (node (ref "U2") (pin "20") (pinfunction "MIC1N_20") (pintype "passive+no_connect"))
    )
    (net (code "149") (name "unconnected-(U2-MIC1P-Pad19)") (class "Default")
      (node (ref "U2") (pin "19") (pinfunction "MIC1P_19") (pintype "passive+no_connect"))
    )
    (net (code "150") (name "unconnected-(U2-PCM_CLK-Pad46)") (class "Default")
      (node (ref "U2") (pin "46") (pinfunction "PCM_CLK_46") (pintype "passive+no_connect"))
    )
    (net (code "151") (name "unconnected-(U2-PCM_IN-Pad47)") (class "Default")
      (node (ref "U2") (pin "47") (pinfunction "PCM_IN_47") (pintype "passive+no_connect"))
    )
    (net (code "152") (name "unconnected-(U2-PCM_OUT-Pad48)") (class "Default")
      (node (ref "U2") (pin "48") (pinfunction "PCM_OUT_48") (pintype "passive+no_connect"))
    )
    (net (code "153") (name "unconnected-(U2-PCM_SYNC-Pad45)") (class "Default")
      (node (ref "U2") (pin "45") (pinfunction "PCM_SYNC_45") (pintype "passive+no_connect"))
    )
    (net (code "154") (name "unconnected-(U2-PWM1-Pad42)") (class "Default")
      (node (ref "U2") (pin "42") (pinfunction "PWM1_42") (pintype "passive+no_connect"))
    )
    (net (code "155") (name "unconnected-(U2-PWM2-Pad41)") (class "Default")
      (node (ref "U2") (pin "41") (pinfunction "PWM2_41") (pintype "passive+no_connect"))
    )
    (net (code "156") (name "unconnected-(U2-RFSYNC-Pad63)") (class "Default")
      (node (ref "U2") (pin "63") (pinfunction "RFSYNC_63") (pintype "passive+no_connect"))
    )
    (net (code "157") (name "unconnected-(U2-RI-Pad10)") (class "Default")
      (node (ref "U2") (pin "10") (pinfunction "RI_10") (pintype "passive+no_connect"))
    )
    (net (code "158") (name "unconnected-(U2-RTS-Pad13)") (class "Default")
      (node (ref "U2") (pin "13") (pinfunction "RTS_13") (pintype "passive+no_connect"))
    )
    (net (code "159") (name "unconnected-(U2-SCL-Pad39)") (class "Default")
      (node (ref "U2") (pin "39") (pinfunction "SCL_39") (pintype "passive+no_connect"))
    )
    (net (code "160") (name "unconnected-(U2-SDA-Pad38)") (class "Default")
      (node (ref "U2") (pin "38") (pinfunction "SDA_38") (pintype "passive+no_connect"))
    )
    (net (code "161") (name "unconnected-(U2-SIM_DET-Pad33)") (class "Default")
      (node (ref "U2") (pin "33") (pinfunction "SIM_DET_33") (pintype "passive+no_connect"))
    )
    (net (code "162") (name "unconnected-(U2-SPK1N-Pad22)") (class "Default")
      (node (ref "U2") (pin "22") (pinfunction "SPK1N_22") (pintype "passive+no_connect"))
    )
    (net (code "163") (name "unconnected-(U2-SPK1P-Pad21)") (class "Default")
      (node (ref "U2") (pin "21") (pinfunction "SPK1P_21") (pintype "passive+no_connect"))
    )
    (net (code "164") (name "unconnected-(U2-USB_DN-Pad27)") (class "Default")
      (node (ref "U2") (pin "27") (pinfunction "USB_DN_27") (pintype "passive+no_connect"))
    )
    (net (code "165") (name "unconnected-(U2-USB_DP-Pad26)") (class "Default")
      (node (ref "U2") (pin "26") (pinfunction "USB_DP_26") (pintype "passive+no_connect"))
    )
    (net (code "166") (name "unconnected-(U2-VCHG-Pad25)") (class "Default")
      (node (ref "U2") (pin "25") (pinfunction "VCHG_25") (pintype "passive+no_connect"))
    )
    (net (code "167") (name "unconnected-(U2-VDD_EXT-Pad7)") (class "Default")
      (node (ref "U2") (pin "7") (pinfunction "VDD_EXT_7") (pintype "passive+no_connect"))
    )
    (net (code "168") (name "unconnected-(U6-TD-Pad4)") (class "Default")
      (node (ref "U6") (pin "4") (pinfunction "TD_4") (pintype "passive+no_connect"))
    )
    (net (code "169") (name "unconnected-(U7-D1{slash}D2-Pad2)") (class "Default")
      (node (ref "U7") (pin "2") (pinfunction "D1/D2_2") (pintype "passive+no_connect"))
    )
    (net (code "170") (name "unconnected-(U7-D1{slash}D2-Pad5)") (class "Default")
      (node (ref "U7") (pin "5") (pinfunction "D1/D2_5") (pintype "passive+no_connect"))
    )
    (net (code "171") (name "unconnected-(U8-CHR0-Pad15)") (class "Default")
      (node (ref "U8") (pin "15") (pinfunction "CHR0_15") (pintype "passive+no_connect"))
    )
    (net (code "172") (name "unconnected-(U8-CHR1-Pad14)") (class "Default")
      (node (ref "U8") (pin "14") (pinfunction "CHR1_14") (pintype "passive+no_connect"))
    )
    (net (code "173") (name "unconnected-(U8-CHREN-Pad13)") (class "Default")
      (node (ref "U8") (pin "13") (pinfunction "CHREN_13") (pintype "passive+no_connect"))
    )
    (net (code "174") (name "unconnected-(U8-GPIO.2_{slash}_RS485-Pad17)") (class "Default")
      (node (ref "U8") (pin "17") (pinfunction "GPIO.2_/_RS485_17") (pintype "passive+no_connect"))
    )
    (net (code "175") (name "unconnected-(U8-GPIO.3_{slash}_WAKEUP-Pad16)") (class "Default")
      (node (ref "U8") (pin "16") (pinfunction "GPIO.3_/_WAKEUP_16") (pintype "passive+no_connect"))
    )
    (net (code "176") (name "unconnected-(U8-GPIO.4-Pad22)") (class "Default")
      (node (ref "U8") (pin "22") (pinfunction "GPIO.4_22") (pintype "passive+no_connect"))
    )
    (net (code "177") (name "unconnected-(U8-GPIO.5-Pad21)") (class "Default")
      (node (ref "U8") (pin "21") (pinfunction "GPIO.5_21") (pintype "passive+no_connect"))
    )
    (net (code "178") (name "unconnected-(U8-GPIO.6-Pad20)") (class "Default")
      (node (ref "U8") (pin "20") (pinfunction "GPIO.6_20") (pintype "passive+no_connect"))
    )
    (net (code "179") (name "unconnected-(U8-NC-Pad10)") (class "Default")
      (node (ref "U8") (pin "10") (pinfunction "NC_10") (pintype "passive+no_connect"))
    )
    (net (code "180") (name "unconnected-(U8-SUSPEND-Pad12)") (class "Default")
      (node (ref "U8") (pin "12") (pinfunction "SUSPEND_12") (pintype "passive+no_connect"))
    )
    (net (code "181") (name "unconnected-(U10-Pad5)") (class "Default")
      (node (ref "U10") (pin "5") (pinfunction "5_5") (pintype "passive+no_connect"))
    )
  )
)
